# MSP-EXP430F5529LP.net
KiCad netlist of a schematic drawn in EAGLE
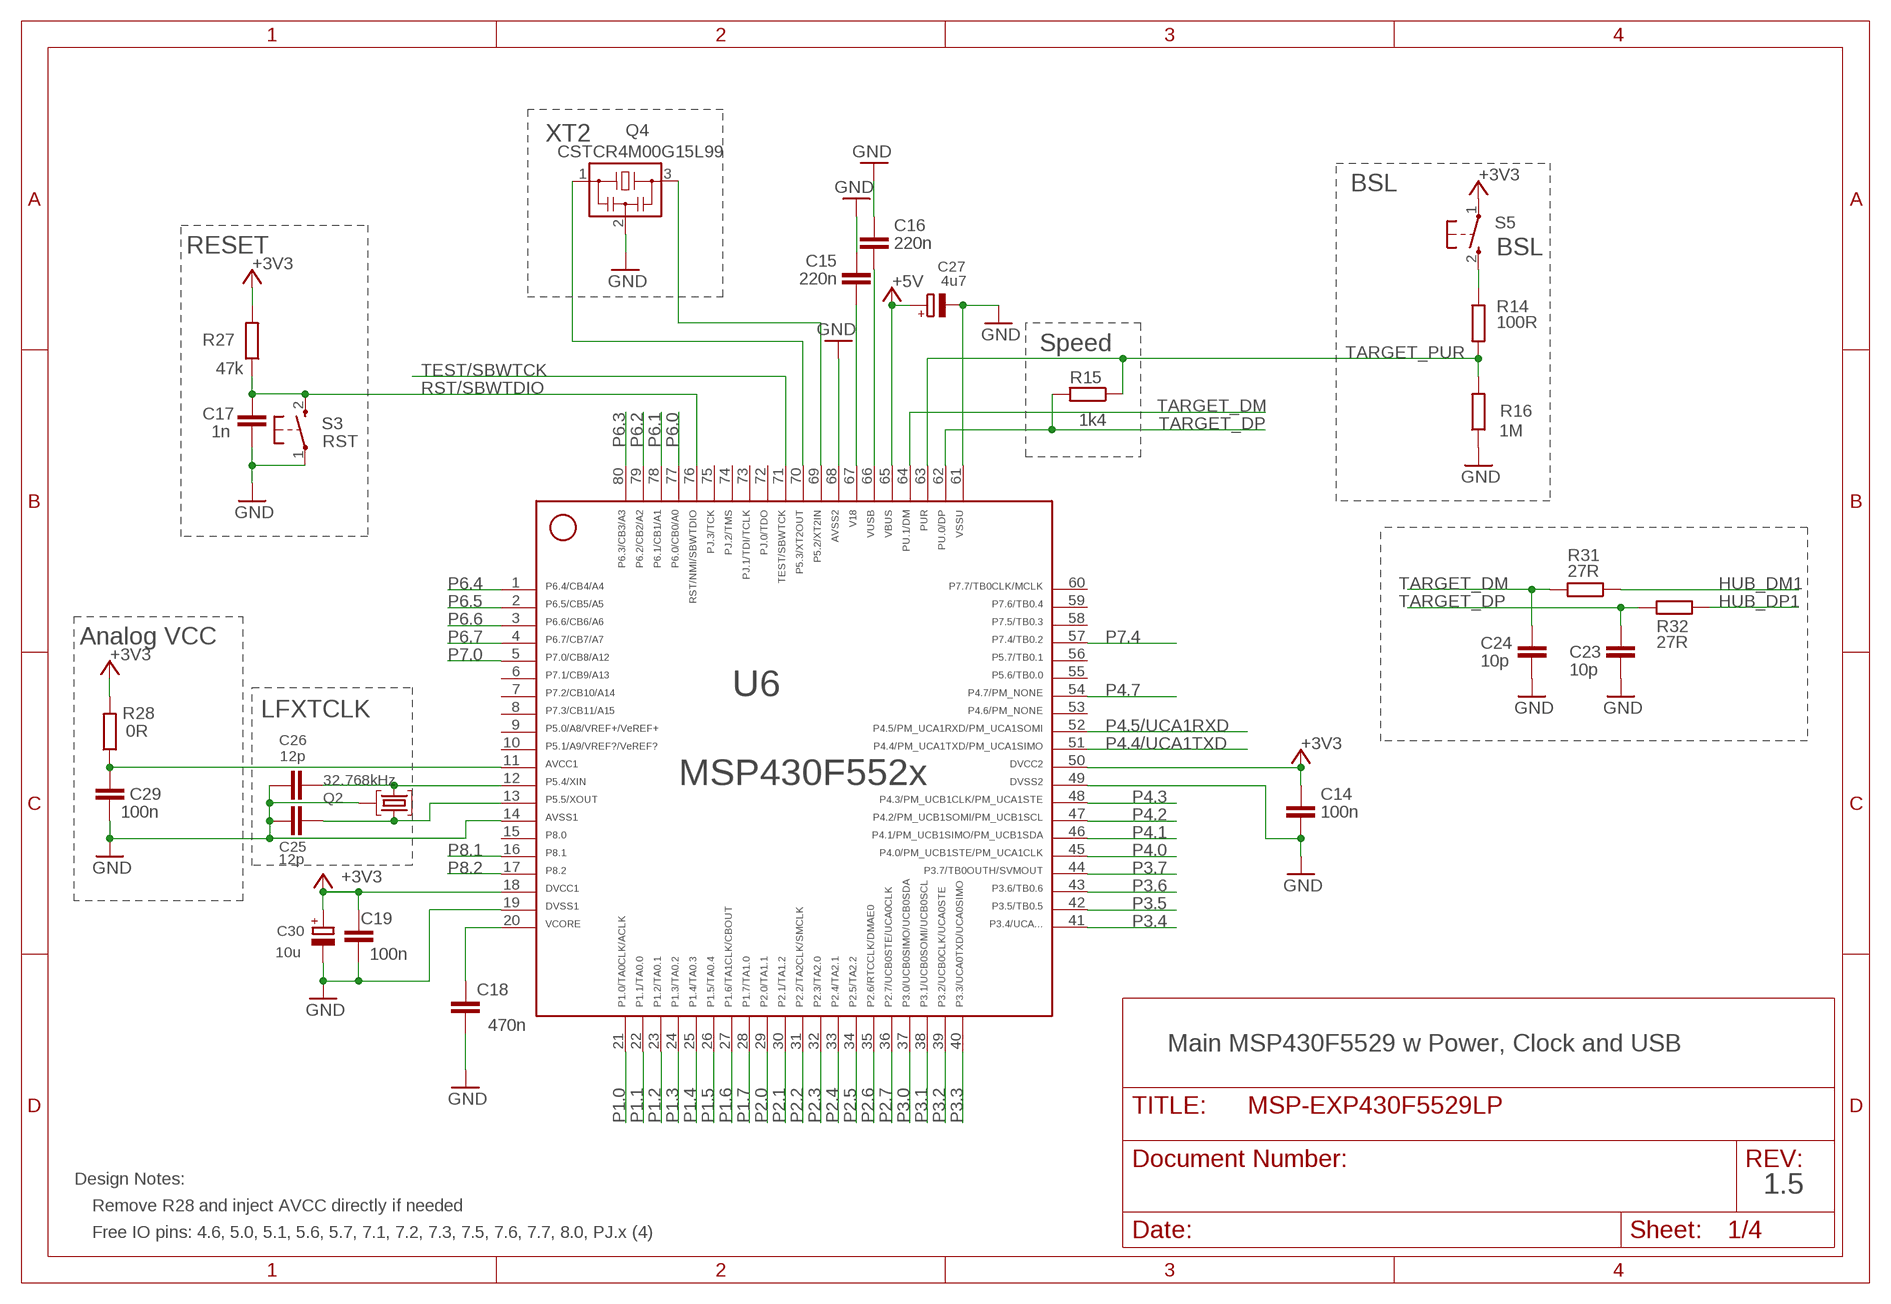
[diagram p0: schematic, sheet 1]
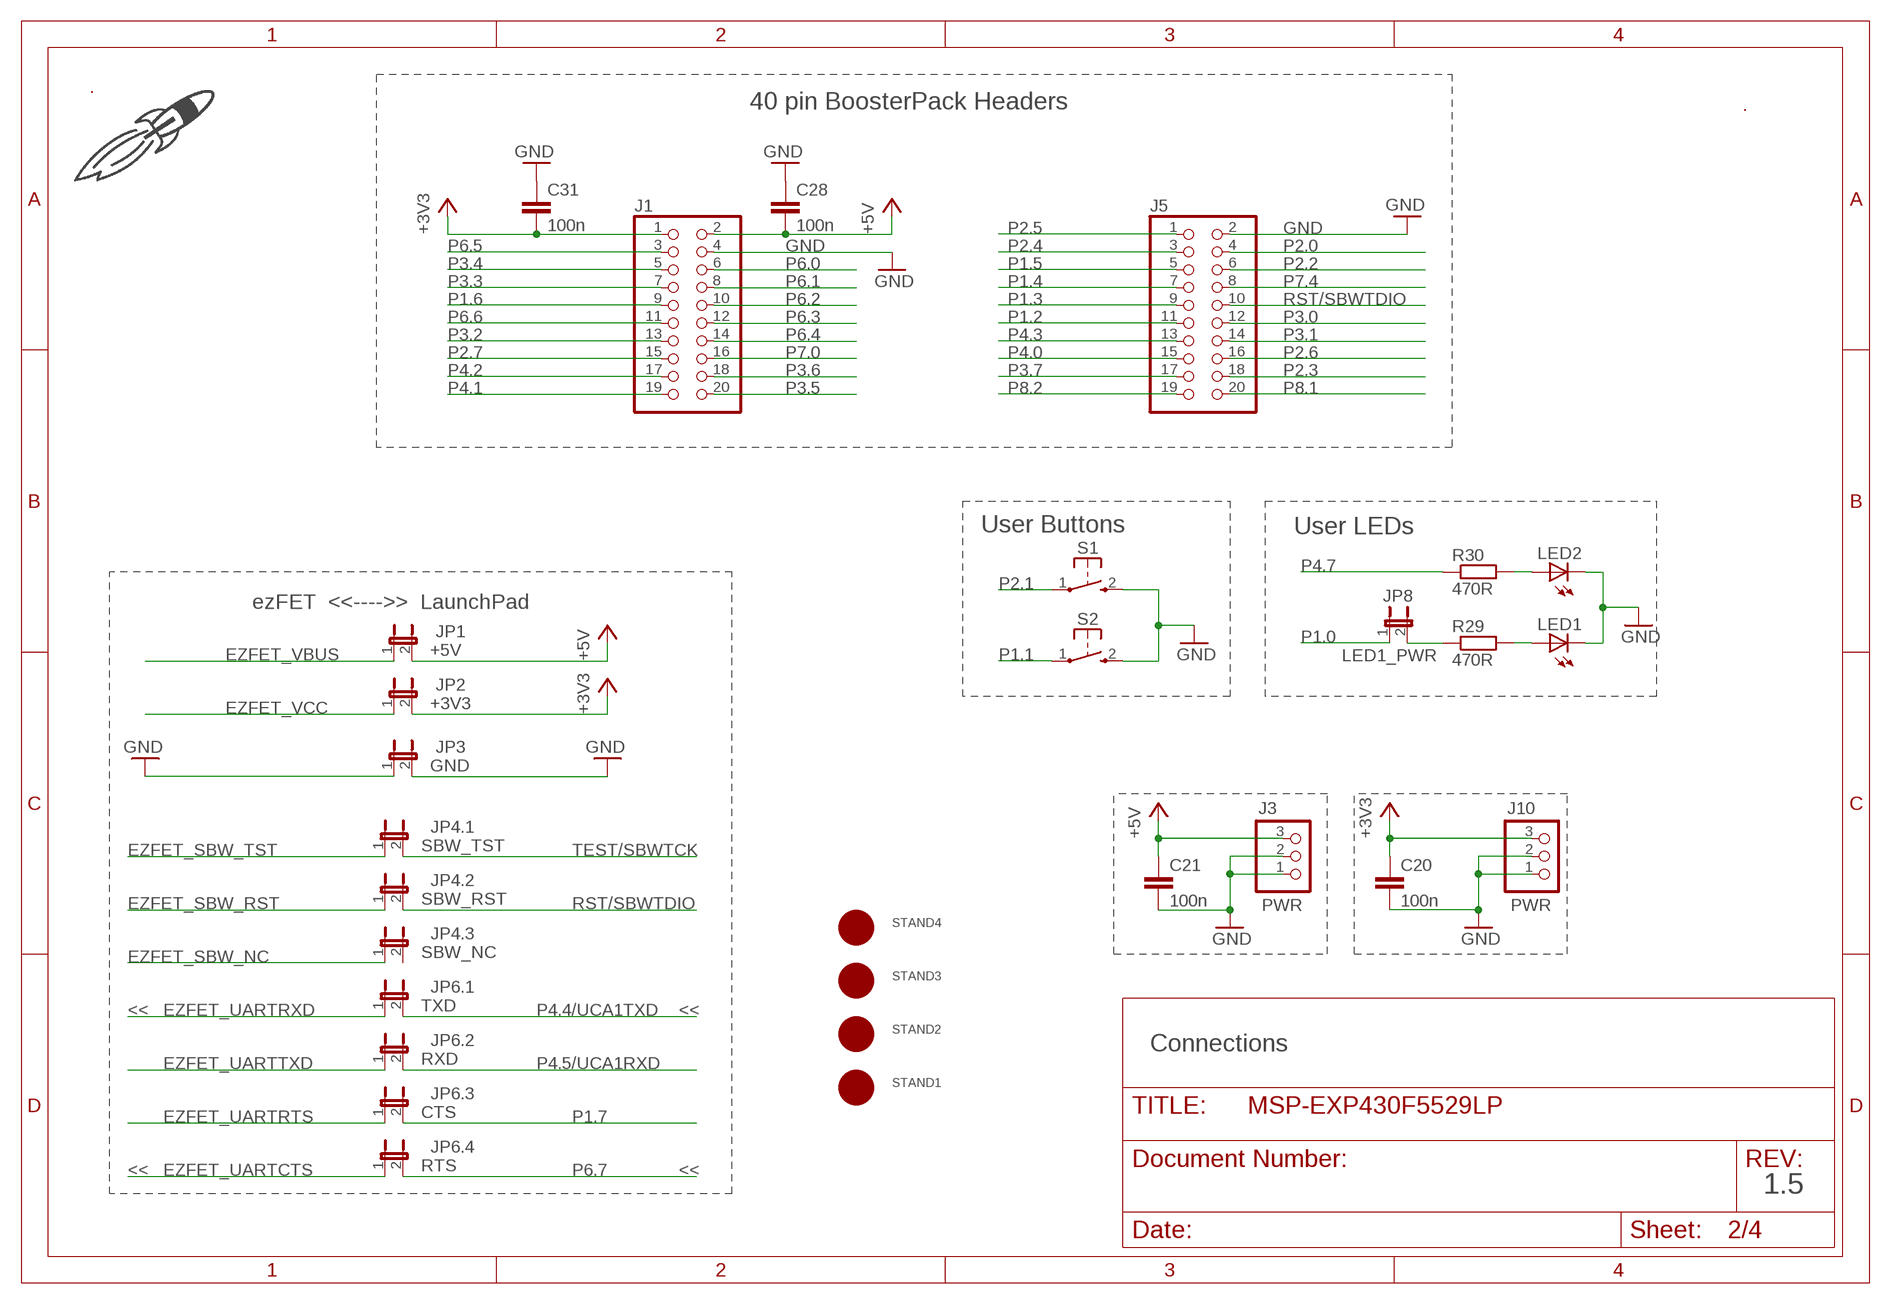
[diagram p1: schematic, sheet 2]
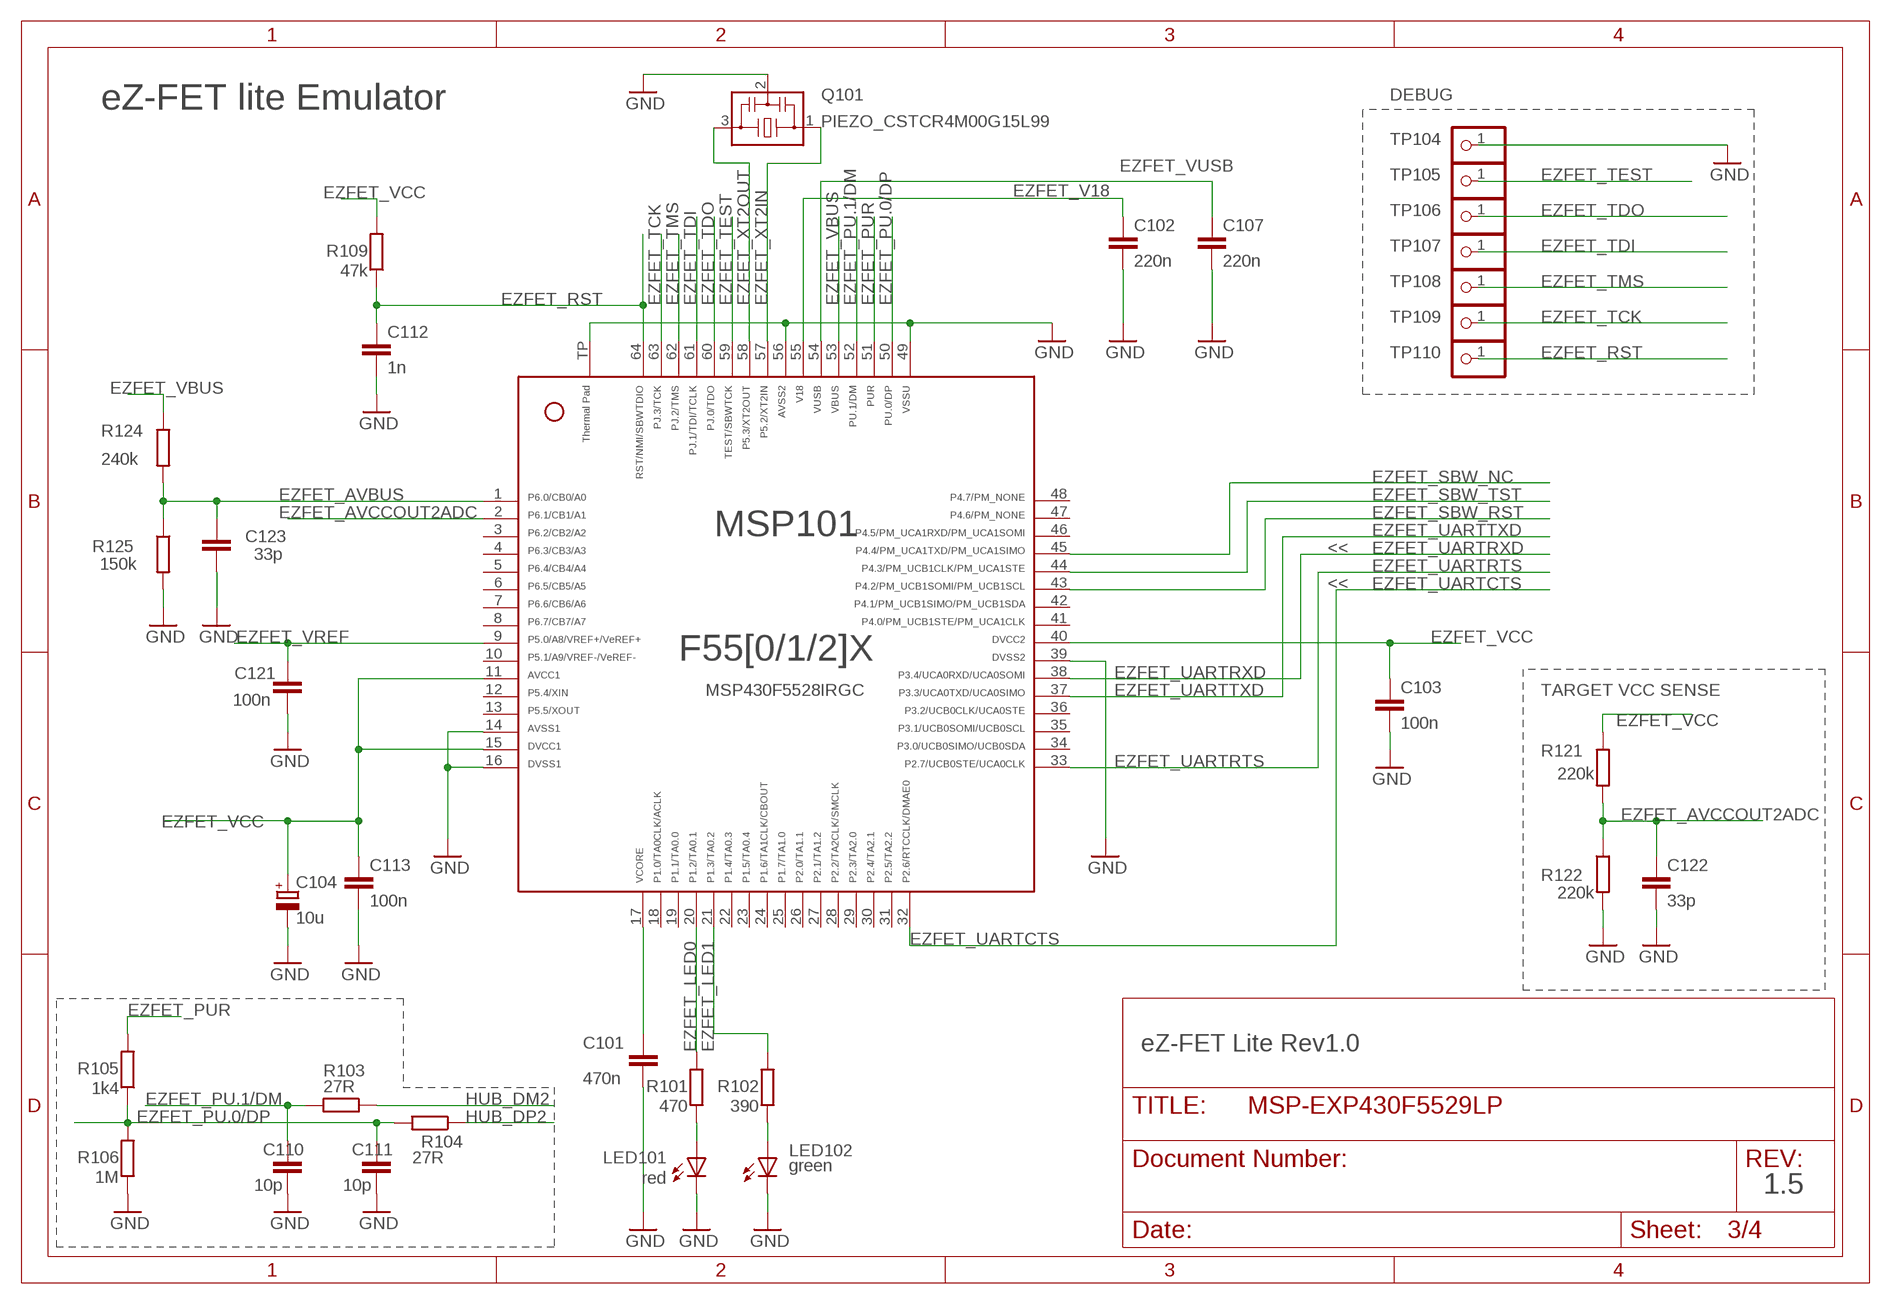
[diagram p2: schematic, sheet 3]
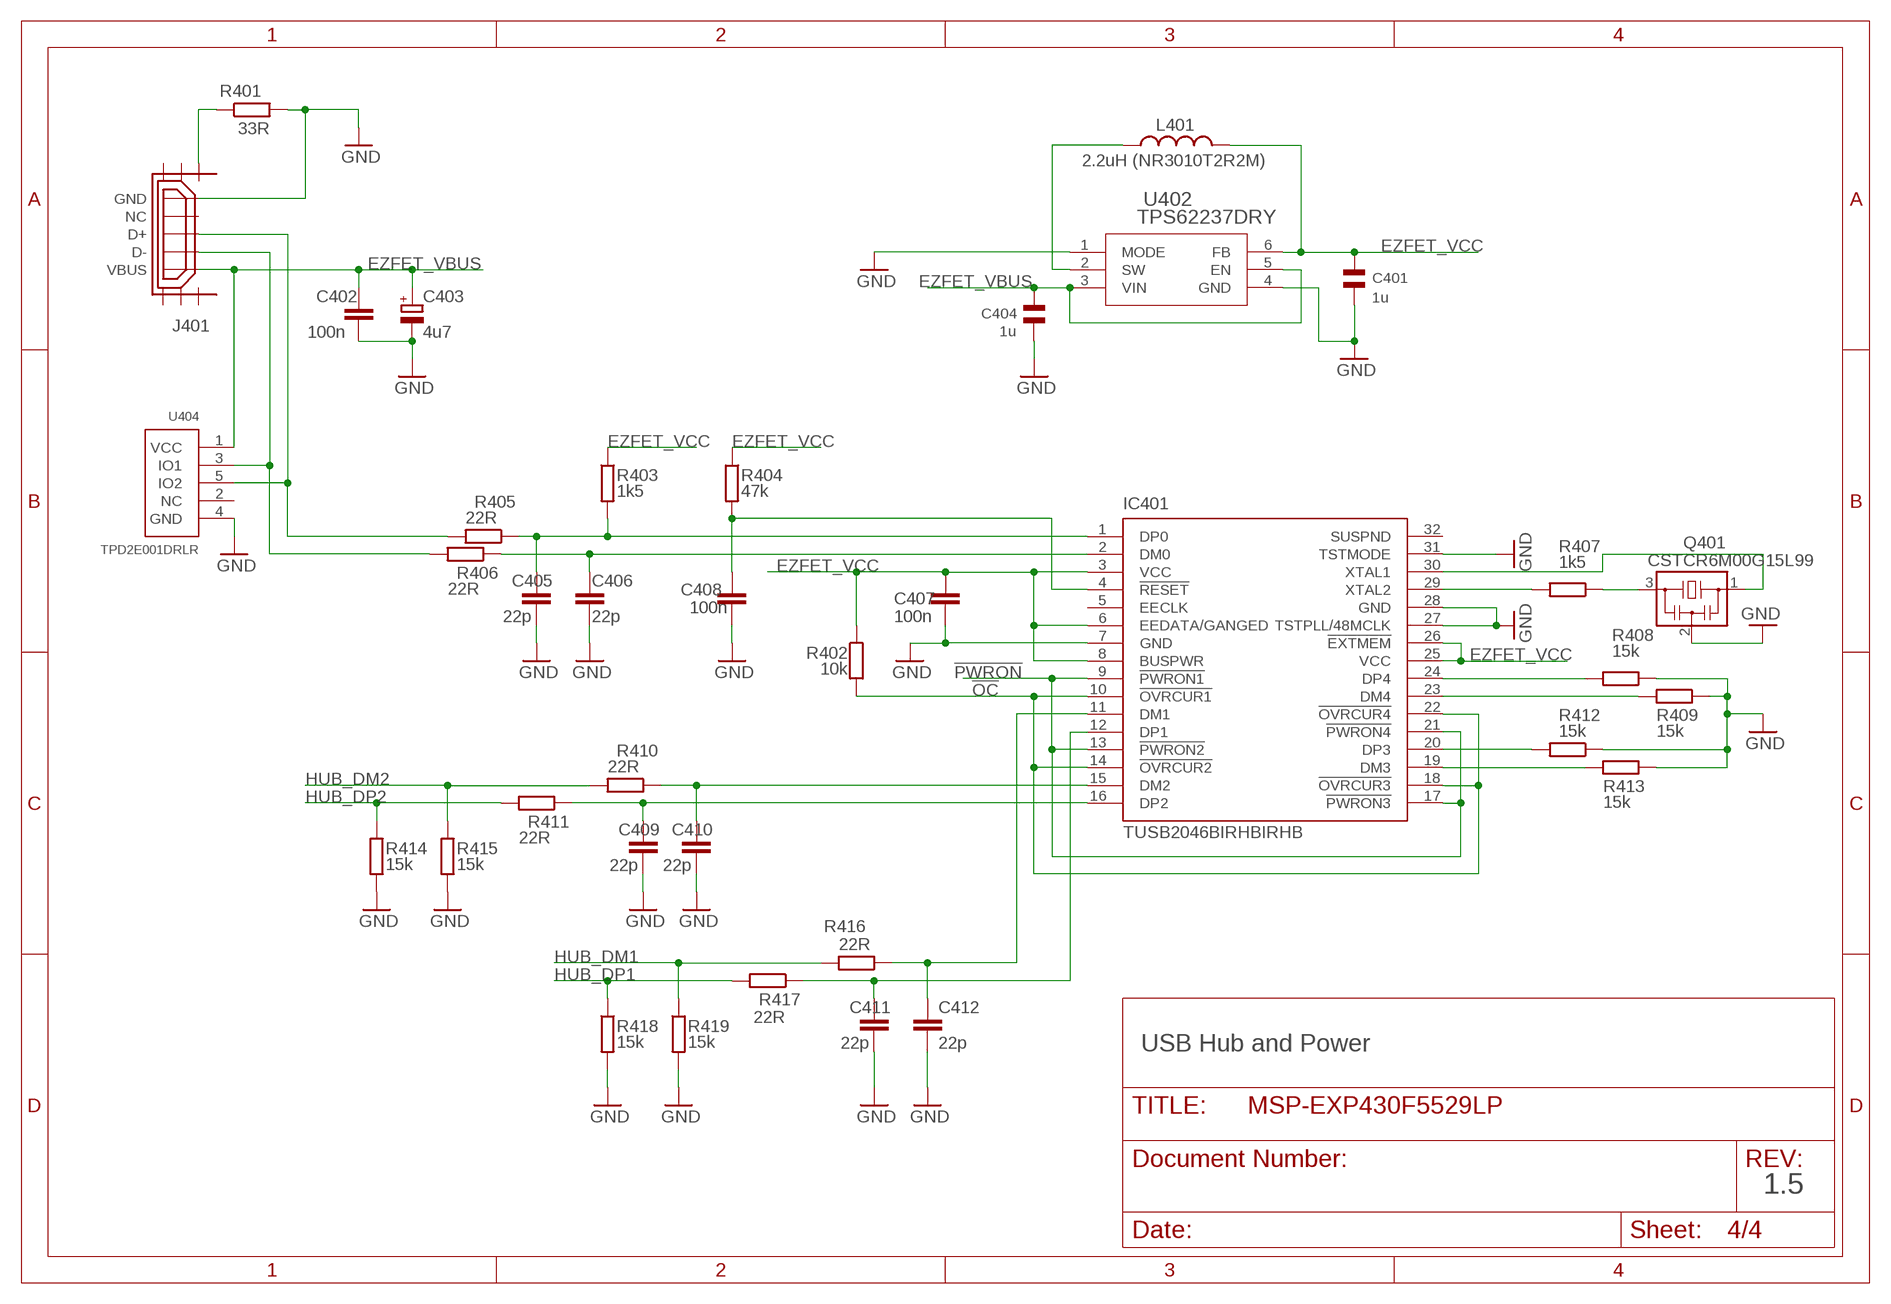
[diagram p3: schematic, sheet 4]

(export (version "E")
  (design (tool "Eeschema 10.0.6"))
  (components
    (comp (ref "C20")
      (value "100n")
      (footprint "eagle-import:C0402")
      (libsource (lib "eagle-import") (part "C-EUC0402"))
    )
    (comp (ref "C21")
      (value "100n")
      (footprint "eagle-import:C0402")
      (libsource (lib "eagle-import") (part "C-EUC0402"))
    )
    (comp (ref "C28")
      (value "100n")
      (footprint "eagle-import:C0402")
      (libsource (lib "eagle-import") (part "C-EUC0402"))
    )
    (comp (ref "C31")
      (value "100n")
      (footprint "eagle-import:C0402")
      (libsource (lib "eagle-import") (part "C-EUC0402"))
    )
    (comp (ref "DRAW1")
      (value "LOGO-ROCKET-20X13MM-SCH-S")
      (footprint "eagle-import:LOGO-ROCKET-10X7MM-BRD")
      (libsource (lib "eagle-import") (part "LOGO-ROCKET-20X13MM-SCH-S"))
    )
    (comp (ref "J1")
      (value "PINHD-2X10")
      (footprint "eagle-import:2X10")
      (libsource (lib "eagle-import") (part "PINHD-2X10"))
    )
    (comp (ref "J3")
      (value "PWR")
      (footprint "eagle-import:1X03")
      (libsource (lib "eagle-import") (part "PINHD-1X3"))
    )
    (comp (ref "J5")
      (value "PINHD-2X10")
      (footprint "eagle-import:2X10")
      (libsource (lib "eagle-import") (part "PINHD-2X10"))
    )
    (comp (ref "J10")
      (value "PWR")
      (footprint "eagle-import:1X03")
      (libsource (lib "eagle-import") (part "PINHD-1X3"))
    )
    (comp (ref "JP1")
      (value "+5V")
      (footprint "eagle-import:JP1M")
      (libsource (lib "eagle-import") (part "JP1M"))
    )
    (comp (ref "JP2")
      (value "+3V3")
      (footprint "eagle-import:JP1M")
      (libsource (lib "eagle-import") (part "JP1M"))
    )
    (comp (ref "JP3")
      (value "GND")
      (footprint "eagle-import:JP1M")
      (libsource (lib "eagle-import") (part "JP1M"))
    )
    (comp (ref "JP4.1")
      (value "SBW_TST")
      (footprint "eagle-import:JP1M")
      (libsource (lib "eagle-import") (part "JP1M"))
    )
    (comp (ref "JP4.2")
      (value "SBW_RST")
      (footprint "eagle-import:JP1M")
      (libsource (lib "eagle-import") (part "JP1M"))
    )
    (comp (ref "JP4.3")
      (value "SBW_NC")
      (footprint "eagle-import:JP1M")
      (libsource (lib "eagle-import") (part "JP1M"))
    )
    (comp (ref "JP6.1")
      (value "TXD")
      (footprint "eagle-import:JP1M")
      (libsource (lib "eagle-import") (part "JP1M"))
    )
    (comp (ref "JP6.2")
      (value "RXD")
      (footprint "eagle-import:JP1M")
      (libsource (lib "eagle-import") (part "JP1M"))
    )
    (comp (ref "JP6.3")
      (value "CTS")
      (footprint "eagle-import:JP1M")
      (libsource (lib "eagle-import") (part "JP1M"))
    )
    (comp (ref "JP6.4")
      (value "RTS")
      (footprint "eagle-import:JP1M")
      (libsource (lib "eagle-import") (part "JP1M"))
    )
    (comp (ref "JP8")
      (value "LED1_PWR")
      (footprint "eagle-import:JP1")
      (libsource (lib "eagle-import") (part "JP1E"))
    )
    (comp (ref "LED1")
      (value "LEDCHIP-LED0603")
      (footprint "eagle-import:CHIP-LED0603")
      (libsource (lib "eagle-import") (part "LEDCHIP-LED0603"))
    )
    (comp (ref "LED2")
      (value "LEDCHIP-LED0603")
      (footprint "eagle-import:CHIP-LED0603")
      (libsource (lib "eagle-import") (part "LEDCHIP-LED0603"))
    )
    (comp (ref "R29")
      (value "470R")
      (footprint "eagle-import:R0402")
      (libsource (lib "eagle-import") (part "R-EU_R0402"))
    )
    (comp (ref "R30")
      (value "470R")
      (footprint "eagle-import:R0402")
      (libsource (lib "eagle-import") (part "R-EU_R0402"))
    )
    (comp (ref "S1")
      (value "PB")
      (footprint "eagle-import:PBTH")
      (libsource (lib "eagle-import") (part "PB"))
    )
    (comp (ref "S2")
      (value "PB")
      (footprint "eagle-import:PBTH")
      (libsource (lib "eagle-import") (part "PB"))
    )
    (comp (ref "STAND1")
      (value "MOUNT")
      (footprint "eagle-import:MOUNTHOLE_110MIL")
      (libsource (lib "eagle-import") (part "MOUNT"))
    )
    (comp (ref "STAND2")
      (value "MOUNT")
      (footprint "eagle-import:MOUNTHOLE_110MIL")
      (libsource (lib "eagle-import") (part "MOUNT"))
    )
    (comp (ref "STAND3")
      (value "MOUNT")
      (footprint "eagle-import:MOUNTHOLE_110MIL")
      (libsource (lib "eagle-import") (part "MOUNT"))
    )
    (comp (ref "STAND4")
      (value "MOUNT")
      (footprint "eagle-import:MOUNTHOLE_110MIL")
      (libsource (lib "eagle-import") (part "MOUNT"))
    )
    (comp (ref "U$3")
      (value "5529_REAR_SILK_REV1_5_FINAL")
      (footprint "eagle-import:5529_REAR_SILK_REV1_5_FINAL")
      (libsource (lib "eagle-import") (part "5529_REAR_SILK_REV1_5_FINAL"))
    )
    (comp (ref "U$4")
      (value "MS_TM")
      (footprint "eagle-import:MS_TM")
      (libsource (lib "eagle-import") (part "MS_TM"))
    )
    (comp (ref "C401")
      (value "1u")
      (footprint "eagle-import:CSMD0805")
      (libsource (lib "eagle-import") (part "CSMD0805"))
    )
    (comp (ref "C402")
      (value "100n")
      (footprint "eagle-import:C0402")
      (libsource (lib "eagle-import") (part "C-EUC0402"))
    )
    (comp (ref "C403")
      (value "4u7")
      (footprint "eagle-import:A_3216-18R")
      (libsource (lib "eagle-import") (part "CPOL-EUA/3216-18R"))
    )
    (comp (ref "C404")
      (value "1u")
      (footprint "eagle-import:CSMD0805")
      (libsource (lib "eagle-import") (part "CSMD0805"))
    )
    (comp (ref "C405")
      (value "22p")
      (footprint "eagle-import:C0402")
      (libsource (lib "eagle-import") (part "C-EUC0402"))
    )
    (comp (ref "C406")
      (value "22p")
      (footprint "eagle-import:C0402")
      (libsource (lib "eagle-import") (part "C-EUC0402"))
    )
    (comp (ref "C407")
      (value "100n")
      (footprint "eagle-import:C0402")
      (libsource (lib "eagle-import") (part "C-EUC0402"))
    )
    (comp (ref "C408")
      (value "100n")
      (footprint "eagle-import:C0402")
      (libsource (lib "eagle-import") (part "C-EUC0402"))
    )
    (comp (ref "C409")
      (value "22p")
      (footprint "eagle-import:C0402")
      (libsource (lib "eagle-import") (part "C-EUC0402"))
    )
    (comp (ref "C410")
      (value "22p")
      (footprint "eagle-import:C0402")
      (libsource (lib "eagle-import") (part "C-EUC0402"))
    )
    (comp (ref "C411")
      (value "22p")
      (footprint "eagle-import:C0402")
      (libsource (lib "eagle-import") (part "C-EUC0402"))
    )
    (comp (ref "C412")
      (value "22p")
      (footprint "eagle-import:C0402")
      (libsource (lib "eagle-import") (part "C-EUC0402"))
    )
    (comp (ref "IC401")
      (value "TUSB2046BIRHBIRHB")
      (footprint "eagle-import:RHB_S-PQFP-N32")
      (fields (field (name "MPN") "TUSB2046BIRHBT"))
      (libsource (lib "eagle-import") (part "TUSB2046BIRHBIRHB"))
    )
    (comp (ref "J401")
      (value "USB_MICRO_FLIPPED")
      (footprint "eagle-import:HIROSE-ZX62R-B-5P")
      (libsource (lib "eagle-import") (part "USB_MICRO_FLIPPED"))
    )
    (comp (ref "L401")
      (value "2.2uH (NR3010T2R2M)")
      (footprint "eagle-import:L-NR3010")
      (libsource (lib "eagle-import") (part "L-NR3010"))
    )
    (comp (ref "Q401")
      (value "CSTCR6M00G15L99")
      (footprint "eagle-import:MURATA-FILTER_CSTCR")
      (fields (field (name "MPN") "CSTCR6M00G53-R0"))
      (libsource (lib "eagle-import") (part "MURATA-FILTER_CSTCR6M00G53Z"))
    )
    (comp (ref "R401")
      (value "33R")
      (footprint "eagle-import:R0402")
      (libsource (lib "eagle-import") (part "R-EU_R0402"))
    )
    (comp (ref "R402")
      (value "10k")
      (footprint "eagle-import:R0402")
      (libsource (lib "eagle-import") (part "R-EU_R0402"))
    )
    (comp (ref "R403")
      (value "1k5")
      (footprint "eagle-import:R0402")
      (libsource (lib "eagle-import") (part "R-EU_R0402"))
    )
    (comp (ref "R404")
      (value "47k")
      (footprint "eagle-import:R0402")
      (libsource (lib "eagle-import") (part "R-EU_R0402"))
    )
    (comp (ref "R405")
      (value "22R")
      (footprint "eagle-import:R0402")
      (libsource (lib "eagle-import") (part "R-EU_R0402"))
    )
    (comp (ref "R406")
      (value "22R")
      (footprint "eagle-import:R0402")
      (libsource (lib "eagle-import") (part "R-EU_R0402"))
    )
    (comp (ref "R407")
      (value "1k5")
      (footprint "eagle-import:R0402")
      (libsource (lib "eagle-import") (part "R-EU_R0402"))
    )
    (comp (ref "R408")
      (value "15k")
      (footprint "eagle-import:R0402")
      (libsource (lib "eagle-import") (part "R-EU_R0402"))
    )
    (comp (ref "R409")
      (value "15k")
      (footprint "eagle-import:R0402")
      (libsource (lib "eagle-import") (part "R-EU_R0402"))
    )
    (comp (ref "R410")
      (value "22R")
      (footprint "eagle-import:R0402")
      (libsource (lib "eagle-import") (part "R-EU_R0402"))
    )
    (comp (ref "R411")
      (value "22R")
      (footprint "eagle-import:R0402")
      (libsource (lib "eagle-import") (part "R-EU_R0402"))
    )
    (comp (ref "R412")
      (value "15k")
      (footprint "eagle-import:R0402")
      (libsource (lib "eagle-import") (part "R-EU_R0402"))
    )
    (comp (ref "R413")
      (value "15k")
      (footprint "eagle-import:R0402")
      (libsource (lib "eagle-import") (part "R-EU_R0402"))
    )
    (comp (ref "R414")
      (value "15k")
      (footprint "eagle-import:R0402")
      (libsource (lib "eagle-import") (part "R-EU_R0402"))
    )
    (comp (ref "R415")
      (value "15k")
      (footprint "eagle-import:R0402")
      (libsource (lib "eagle-import") (part "R-EU_R0402"))
    )
    (comp (ref "R416")
      (value "22R")
      (footprint "eagle-import:R0402")
      (libsource (lib "eagle-import") (part "R-EU_R0402"))
    )
    (comp (ref "R417")
      (value "22R")
      (footprint "eagle-import:R0402")
      (libsource (lib "eagle-import") (part "R-EU_R0402"))
    )
    (comp (ref "R418")
      (value "15k")
      (footprint "eagle-import:R0402")
      (libsource (lib "eagle-import") (part "R-EU_R0402"))
    )
    (comp (ref "R419")
      (value "15k")
      (footprint "eagle-import:R0402")
      (libsource (lib "eagle-import") (part "R-EU_R0402"))
    )
    (comp (ref "U402")
      (value "TPS62237DRY")
      (footprint "eagle-import:DRY6")
      (fields
        (field (name "GENERIC_PART_NUMBER") "TPS62231")
        (field (name "MANUFACTURER") "Texas Instruments")
        (field (name "MANUFACTURER_PART_NUMBER") "tps62231_dry_6")
      )
      (libsource (lib "eagle-import") (part "TPS6223X_DRY_6"))
    )
    (comp (ref "U404")
      (value "TPD2E001DRLR")
      (footprint "eagle-import:TPD2E001-DRL")
      (libsource (lib "eagle-import") (part "TPD2E001"))
    )
    (comp (ref "C14")
      (value "100n")
      (footprint "eagle-import:C0402")
      (libsource (lib "eagle-import") (part "C-EUC0402"))
    )
    (comp (ref "C15")
      (value "220n")
      (footprint "eagle-import:C0402")
      (libsource (lib "eagle-import") (part "C-EUC0402"))
    )
    (comp (ref "C16")
      (value "220n")
      (footprint "eagle-import:C0402")
      (libsource (lib "eagle-import") (part "C-EUC0402"))
    )
    (comp (ref "C17")
      (value "1n")
      (footprint "eagle-import:C0402")
      (libsource (lib "eagle-import") (part "C-EUC0402"))
    )
    (comp (ref "C18")
      (value "470n")
      (footprint "eagle-import:C0402")
      (libsource (lib "eagle-import") (part "C-EUC0402"))
    )
    (comp (ref "C19")
      (value "100n")
      (footprint "eagle-import:C0402")
      (libsource (lib "eagle-import") (part "C-EUC0402"))
    )
    (comp (ref "C23")
      (value "10p")
      (footprint "eagle-import:C0402")
      (libsource (lib "eagle-import") (part "C-EUC0402"))
    )
    (comp (ref "C24")
      (value "10p")
      (footprint "eagle-import:C0402")
      (libsource (lib "eagle-import") (part "C-EUC0402"))
    )
    (comp (ref "C25")
      (value "12p")
      (footprint "eagle-import:C0402")
      (libsource (lib "eagle-import") (part "C-EUC0402"))
    )
    (comp (ref "C26")
      (value "12p")
      (footprint "eagle-import:C0402")
      (libsource (lib "eagle-import") (part "C-EUC0402"))
    )
    (comp (ref "C27")
      (value "4u7")
      (footprint "eagle-import:A_3216-18R")
      (libsource (lib "eagle-import") (part "CPOL-EUA/3216-18R"))
    )
    (comp (ref "C29")
      (value "100n")
      (footprint "eagle-import:C0402")
      (libsource (lib "eagle-import") (part "C-EUC0402"))
    )
    (comp (ref "C30")
      (value "10u")
      (footprint "eagle-import:A_3216-18R")
      (libsource (lib "eagle-import") (part "CPOL-EUA/3216-18R"))
    )
    (comp (ref "Q2")
      (value "32.768kHz")
      (footprint "eagle-import:MS3V-T1R")
      (libsource (lib "eagle-import") (part "MS3V-T1R"))
    )
    (comp (ref "Q4")
      (value "CSTCR4M00G15L99")
      (footprint "eagle-import:MURATA-FILTER_CSTCR")
      (fields (field (name "MPN") "CSTCR6M00G53-R0"))
      (libsource (lib "eagle-import") (part "MURATA-FILTER_CSTCR6M00G53Z"))
    )
    (comp (ref "R14")
      (value "100R")
      (footprint "eagle-import:R0402")
      (libsource (lib "eagle-import") (part "R-EU_R0402"))
    )
    (comp (ref "R15")
      (value "1k4")
      (footprint "eagle-import:R0402")
      (libsource (lib "eagle-import") (part "R-EU_R0402"))
    )
    (comp (ref "R16")
      (value "1M")
      (footprint "eagle-import:R0402")
      (libsource (lib "eagle-import") (part "R-EU_R0402"))
    )
    (comp (ref "R27")
      (value "47k")
      (footprint "eagle-import:R0402")
      (libsource (lib "eagle-import") (part "R-EU_R0402"))
    )
    (comp (ref "R28")
      (value "0R")
      (footprint "eagle-import:R0402")
      (libsource (lib "eagle-import") (part "R-EU_R0402"))
    )
    (comp (ref "R31")
      (value "27R")
      (footprint "eagle-import:R0402")
      (libsource (lib "eagle-import") (part "R-EU_R0402"))
    )
    (comp (ref "R32")
      (value "27R")
      (footprint "eagle-import:R0402")
      (libsource (lib "eagle-import") (part "R-EU_R0402"))
    )
    (comp (ref "S3")
      (value "RST")
      (footprint "eagle-import:PBTH")
      (libsource (lib "eagle-import") (part "PB"))
    )
    (comp (ref "S5")
      (value "BSL")
      (footprint "eagle-import:PBTH")
      (libsource (lib "eagle-import") (part "PB"))
    )
    (comp (ref "U6")
      (value "MSP430F5529IPNR")
      (footprint "eagle-import:PN80")
      (libsource (lib "eagle-import") (part "F552X---PN80"))
    )
    (comp (ref "C101")
      (value "470n")
      (footprint "eagle-import:C0402")
      (libsource (lib "eagle-import") (part "C-EUC0402"))
    )
    (comp (ref "C102")
      (value "220n")
      (footprint "eagle-import:C0402")
      (libsource (lib "eagle-import") (part "C-EUC0402"))
    )
    (comp (ref "C103")
      (value "100n")
      (footprint "eagle-import:C0402")
      (libsource (lib "eagle-import") (part "C-EUC0402"))
    )
    (comp (ref "C104")
      (value "10u")
      (footprint "eagle-import:A_3216-18R")
      (libsource (lib "eagle-import") (part "CPOL-EUA/3216-18R"))
    )
    (comp (ref "C107")
      (value "220n")
      (footprint "eagle-import:C0402")
      (libsource (lib "eagle-import") (part "C-EUC0402"))
    )
    (comp (ref "C110")
      (value "10p")
      (footprint "eagle-import:C0402")
      (libsource (lib "eagle-import") (part "C-EUC0402"))
    )
    (comp (ref "C111")
      (value "10p")
      (footprint "eagle-import:C0402")
      (libsource (lib "eagle-import") (part "C-EUC0402"))
    )
    (comp (ref "C112")
      (value "1n")
      (footprint "eagle-import:C0402")
      (libsource (lib "eagle-import") (part "C-EUC0402"))
    )
    (comp (ref "C113")
      (value "100n")
      (footprint "eagle-import:C0402")
      (libsource (lib "eagle-import") (part "C-EUC0402"))
    )
    (comp (ref "C121")
      (value "100n")
      (footprint "eagle-import:C0402")
      (libsource (lib "eagle-import") (part "C-EUC0402"))
    )
    (comp (ref "C122")
      (value "33p")
      (footprint "eagle-import:C0402")
      (libsource (lib "eagle-import") (part "C-EUC0402"))
    )
    (comp (ref "C123")
      (value "33p")
      (footprint "eagle-import:C0402")
      (libsource (lib "eagle-import") (part "C-EUC0402"))
    )
    (comp (ref "LED101")
      (value "red")
      (footprint "eagle-import:CHIP-LED0603")
      (libsource (lib "eagle-import") (part "LEDCHIP-LED0603"))
    )
    (comp (ref "LED102")
      (value "green")
      (footprint "eagle-import:CHIP-LED0603")
      (libsource (lib "eagle-import") (part "LEDCHIP-LED0603"))
    )
    (comp (ref "MSP101")
      (value "MSP430F5528IRGC")
      (footprint "eagle-import:RGC64")
      (libsource (lib "eagle-import") (part "F55[0/1/2]X---RGC64"))
    )
    (comp (ref "Q101")
      (value "PIEZO_CSTCR4M00G15L99")
      (footprint "eagle-import:MURATA-FILTER_CSTCR")
      (fields (field (name "MPN") "CSTCR6M00G53-R0"))
      (libsource (lib "eagle-import") (part "MURATA-FILTER_CSTCR6M00G53Z"))
    )
    (comp (ref "R101")
      (value "470")
      (footprint "eagle-import:R0402")
      (libsource (lib "eagle-import") (part "R-EU_R0402"))
    )
    (comp (ref "R102")
      (value "390")
      (footprint "eagle-import:R0402")
      (libsource (lib "eagle-import") (part "R-EU_R0402"))
    )
    (comp (ref "R103")
      (value "27R")
      (footprint "eagle-import:R0402")
      (libsource (lib "eagle-import") (part "R-EU_R0402"))
    )
    (comp (ref "R104")
      (value "27R")
      (footprint "eagle-import:R0402")
      (libsource (lib "eagle-import") (part "R-EU_R0402"))
    )
    (comp (ref "R105")
      (value "1k4")
      (footprint "eagle-import:R0402")
      (libsource (lib "eagle-import") (part "R-EU_R0402"))
    )
    (comp (ref "R106")
      (value "1M")
      (footprint "eagle-import:R0402")
      (libsource (lib "eagle-import") (part "R-EU_R0402"))
    )
    (comp (ref "R109")
      (value "47k")
      (footprint "eagle-import:R0402")
      (libsource (lib "eagle-import") (part "R-EU_R0402"))
    )
    (comp (ref "R121")
      (value "220k")
      (footprint "eagle-import:R0402")
      (libsource (lib "eagle-import") (part "R-EU_R0402"))
    )
    (comp (ref "R122")
      (value "220k")
      (footprint "eagle-import:R0402")
      (libsource (lib "eagle-import") (part "R-EU_R0402"))
    )
    (comp (ref "R124")
      (value "240k")
      (footprint "eagle-import:R0402")
      (libsource (lib "eagle-import") (part "R-EU_R0402"))
    )
    (comp (ref "R125")
      (value "150k")
      (footprint "eagle-import:R0402")
      (libsource (lib "eagle-import") (part "R-EU_R0402"))
    )
    (comp (ref "TP104")
      (value "TEST_PIN2")
      (footprint "eagle-import:1X01")
      (libsource (lib "eagle-import") (part "PINHD-1X1"))
    )
    (comp (ref "TP105")
      (value "TEST_PIN2")
      (footprint "eagle-import:1X01")
      (libsource (lib "eagle-import") (part "PINHD-1X1"))
    )
    (comp (ref "TP106")
      (value "TEST_PIN2")
      (footprint "eagle-import:1X01")
      (libsource (lib "eagle-import") (part "PINHD-1X1"))
    )
    (comp (ref "TP107")
      (value "TEST_PIN2")
      (footprint "eagle-import:1X01")
      (libsource (lib "eagle-import") (part "PINHD-1X1"))
    )
    (comp (ref "TP108")
      (value "TEST_PIN2")
      (footprint "eagle-import:1X01")
      (libsource (lib "eagle-import") (part "PINHD-1X1"))
    )
    (comp (ref "TP109")
      (value "TEST_PIN2")
      (footprint "eagle-import:1X01")
      (libsource (lib "eagle-import") (part "PINHD-1X1"))
    )
    (comp (ref "TP110")
      (value "TEST_PIN2")
      (footprint "eagle-import:1X01")
      (libsource (lib "eagle-import") (part "PINHD-1X1"))
    )
  )
  (nets
    (net (code "1") (name "+3V3") (class "Default")
      (node (ref "C14") (pin "1") (pinfunction "1_1") (pintype "passive"))
      (node (ref "C19") (pin "2") (pinfunction "2_2") (pintype "passive"))
      (node (ref "C20") (pin "1") (pinfunction "1_1") (pintype "passive"))
      (node (ref "C30") (pin "+") (pinfunction "+_+") (pintype "passive"))
      (node (ref "C31") (pin "2") (pinfunction "2_2") (pintype "passive"))
      (node (ref "J1") (pin "1") (pinfunction "1_1") (pintype "passive"))
      (node (ref "J10") (pin "3") (pinfunction "3_3") (pintype "passive"))
      (node (ref "JP2") (pin "2") (pinfunction "2_2") (pintype "passive"))
      (node (ref "R27") (pin "2") (pinfunction "2_2") (pintype "passive"))
      (node (ref "R28") (pin "2") (pinfunction "2_2") (pintype "passive"))
      (node (ref "S5") (pin "1") (pinfunction "P_1") (pintype "passive"))
      (node (ref "U6") (pin "18") (pinfunction "18_18") (pintype "power_in"))
      (node (ref "U6") (pin "50") (pinfunction "50_50") (pintype "power_in"))
    )
    (net (code "2") (name "+5V") (class "Default")
      (node (ref "C21") (pin "1") (pinfunction "1_1") (pintype "passive"))
      (node (ref "C27") (pin "+") (pinfunction "+_+") (pintype "passive"))
      (node (ref "C28") (pin "2") (pinfunction "2_2") (pintype "passive"))
      (node (ref "J1") (pin "2") (pinfunction "2_2") (pintype "passive"))
      (node (ref "J3") (pin "3") (pinfunction "3_3") (pintype "passive"))
      (node (ref "JP1") (pin "2") (pinfunction "2_2") (pintype "passive"))
      (node (ref "U6") (pin "65") (pinfunction "65_65") (pintype "power_in"))
    )
    (net (code "3") (name "EZFET_AVBUS") (class "Default")
      (node (ref "C123") (pin "2") (pinfunction "2_2") (pintype "passive"))
      (node (ref "MSP101") (pin "1") (pinfunction "1_1") (pintype "bidirectional"))
      (node (ref "R124") (pin "2") (pinfunction "2_2") (pintype "passive"))
      (node (ref "R125") (pin "1") (pinfunction "1_1") (pintype "passive"))
    )
    (net (code "4") (name "EZFET_AVCCOUT2ADC") (class "Default")
      (node (ref "C122") (pin "2") (pinfunction "2_2") (pintype "passive"))
      (node (ref "MSP101") (pin "2") (pinfunction "2_2") (pintype "bidirectional"))
      (node (ref "R121") (pin "2") (pinfunction "2_2") (pintype "passive"))
      (node (ref "R122") (pin "1") (pinfunction "1_1") (pintype "passive"))
    )
    (net (code "5") (name "EZFET_LED0") (class "Default")
      (node (ref "MSP101") (pin "20") (pinfunction "20_20") (pintype "bidirectional"))
      (node (ref "R101") (pin "2") (pinfunction "2_2") (pintype "passive"))
    )
    (net (code "6") (name "EZFET_LED1") (class "Default")
      (node (ref "MSP101") (pin "21") (pinfunction "21_21") (pintype "bidirectional"))
      (node (ref "R102") (pin "2") (pinfunction "2_2") (pintype "passive"))
    )
    (net (code "7") (name "EZFET_PU.0{slash}DP") (class "Default")
      (node (ref "C111") (pin "1") (pinfunction "1_1") (pintype "passive"))
      (node (ref "MSP101") (pin "50") (pinfunction "50_50") (pintype "bidirectional"))
      (node (ref "R104") (pin "2") (pinfunction "2_2") (pintype "passive"))
      (node (ref "R105") (pin "1") (pinfunction "1_1") (pintype "passive"))
      (node (ref "R106") (pin "2") (pinfunction "2_2") (pintype "passive"))
    )
    (net (code "8") (name "EZFET_PU.1{slash}DM") (class "Default")
      (node (ref "C110") (pin "1") (pinfunction "1_1") (pintype "passive"))
      (node (ref "MSP101") (pin "52") (pinfunction "52_52") (pintype "bidirectional"))
      (node (ref "R103") (pin "2") (pinfunction "2_2") (pintype "passive"))
    )
    (net (code "9") (name "EZFET_PUR") (class "Default")
      (node (ref "MSP101") (pin "51") (pinfunction "51_51") (pintype "bidirectional"))
      (node (ref "R105") (pin "2") (pinfunction "2_2") (pintype "passive"))
    )
    (net (code "10") (name "EZFET_RST") (class "Default")
      (node (ref "C112") (pin "1") (pinfunction "1_1") (pintype "passive"))
      (node (ref "MSP101") (pin "64") (pinfunction "64_64") (pintype "bidirectional"))
      (node (ref "R109") (pin "1") (pinfunction "1_1") (pintype "passive"))
      (node (ref "TP110") (pin "1") (pinfunction "1_1") (pintype "passive"))
    )
    (net (code "11") (name "EZFET_SBW_NC") (class "Default")
      (node (ref "JP4.3") (pin "1") (pinfunction "1_1") (pintype "passive"))
      (node (ref "MSP101") (pin "45") (pinfunction "45_45") (pintype "bidirectional"))
    )
    (net (code "12") (name "EZFET_SBW_RST") (class "Default")
      (node (ref "JP4.2") (pin "1") (pinfunction "1_1") (pintype "passive"))
      (node (ref "MSP101") (pin "43") (pinfunction "43_43") (pintype "bidirectional"))
    )
    (net (code "13") (name "EZFET_SBW_TST") (class "Default")
      (node (ref "JP4.1") (pin "1") (pinfunction "1_1") (pintype "passive"))
      (node (ref "MSP101") (pin "44") (pinfunction "44_44") (pintype "bidirectional"))
    )
    (net (code "14") (name "EZFET_TCK") (class "Default")
      (node (ref "MSP101") (pin "63") (pinfunction "63_63") (pintype "bidirectional"))
      (node (ref "TP109") (pin "1") (pinfunction "1_1") (pintype "passive"))
    )
    (net (code "15") (name "EZFET_TDI") (class "Default")
      (node (ref "MSP101") (pin "61") (pinfunction "61_61") (pintype "bidirectional"))
      (node (ref "TP107") (pin "1") (pinfunction "1_1") (pintype "passive"))
    )
    (net (code "16") (name "EZFET_TDO") (class "Default")
      (node (ref "MSP101") (pin "60") (pinfunction "60_60") (pintype "bidirectional"))
      (node (ref "TP106") (pin "1") (pinfunction "1_1") (pintype "passive"))
    )
    (net (code "17") (name "EZFET_TEST") (class "Default")
      (node (ref "MSP101") (pin "59") (pinfunction "59_59") (pintype "input"))
      (node (ref "TP105") (pin "1") (pinfunction "1_1") (pintype "passive"))
    )
    (net (code "18") (name "EZFET_TMS") (class "Default")
      (node (ref "MSP101") (pin "62") (pinfunction "62_62") (pintype "bidirectional"))
      (node (ref "TP108") (pin "1") (pinfunction "1_1") (pintype "passive"))
    )
    (net (code "19") (name "EZFET_UARTCTS") (class "Default")
      (node (ref "JP6.4") (pin "1") (pinfunction "1_1") (pintype "passive"))
      (node (ref "MSP101") (pin "32") (pinfunction "32_32") (pintype "bidirectional"))
    )
    (net (code "20") (name "EZFET_UARTRTS") (class "Default")
      (node (ref "JP6.3") (pin "1") (pinfunction "1_1") (pintype "passive"))
      (node (ref "MSP101") (pin "33") (pinfunction "33_33") (pintype "bidirectional"))
    )
    (net (code "21") (name "EZFET_UARTRXD") (class "Default")
      (node (ref "JP6.1") (pin "1") (pinfunction "1_1") (pintype "passive"))
      (node (ref "MSP101") (pin "38") (pinfunction "38_38") (pintype "bidirectional"))
    )
    (net (code "22") (name "EZFET_UARTTXD") (class "Default")
      (node (ref "JP6.2") (pin "1") (pinfunction "1_1") (pintype "passive"))
      (node (ref "MSP101") (pin "37") (pinfunction "37_37") (pintype "bidirectional"))
    )
    (net (code "23") (name "EZFET_V18") (class "Default")
      (node (ref "C102") (pin "1") (pinfunction "1_1") (pintype "passive"))
      (node (ref "MSP101") (pin "55") (pinfunction "55_55") (pintype "power_in"))
    )
    (net (code "24") (name "EZFET_VBUS") (class "Default")
      (node (ref "C402") (pin "1") (pinfunction "1_1") (pintype "passive"))
      (node (ref "C403") (pin "+") (pinfunction "+_+") (pintype "passive"))
      (node (ref "C404") (pin "2") (pinfunction "2_2") (pintype "passive"))
      (node (ref "J401") (pin "VBUS") (pinfunction "VBUS_VBUS") (pintype "input"))
      (node (ref "JP1") (pin "1") (pinfunction "1_1") (pintype "passive"))
      (node (ref "MSP101") (pin "53") (pinfunction "53_53") (pintype "power_in"))
      (node (ref "R124") (pin "1") (pinfunction "1_1") (pintype "passive"))
      (node (ref "U402") (pin "3") (pinfunction "VIN_3") (pintype "power_in"))
      (node (ref "U402") (pin "5") (pinfunction "EN_5") (pintype "input"))
      (node (ref "U404") (pin "1") (pinfunction "VCC_1") (pintype "power_in"))
    )
    (net (code "25") (name "EZFET_VCC") (class "Default")
      (node (ref "C103") (pin "1") (pinfunction "1_1") (pintype "passive"))
      (node (ref "C104") (pin "+") (pinfunction "+_+") (pintype "passive"))
      (node (ref "C113") (pin "1") (pinfunction "1_1") (pintype "passive"))
      (node (ref "C401") (pin "2") (pinfunction "2_2") (pintype "passive"))
      (node (ref "C407") (pin "1") (pinfunction "1_1") (pintype "passive"))
      (node (ref "IC401") (pin "25") (pinfunction "VCC_25") (pintype "power_in"))
      (node (ref "IC401") (pin "26") (pinfunction "~{EXTMEM}_26") (pintype "input"))
      (node (ref "IC401") (pin "3") (pinfunction "VCC_3") (pintype "power_in"))
      (node (ref "IC401") (pin "6") (pinfunction "EEDATA/GANGED_6") (pintype "bidirectional"))
      (node (ref "IC401") (pin "8") (pinfunction "BUSPWR_8") (pintype "input"))
      (node (ref "JP2") (pin "1") (pinfunction "1_1") (pintype "passive"))
      (node (ref "L401") (pin "P$2") (pinfunction "2_P$2") (pintype "passive"))
      (node (ref "MSP101") (pin "11") (pinfunction "11_11") (pintype "power_in"))
      (node (ref "MSP101") (pin "15") (pinfunction "15_15") (pintype "power_in"))
      (node (ref "MSP101") (pin "40") (pinfunction "40_40") (pintype "power_in"))
      (node (ref "R109") (pin "2") (pinfunction "2_2") (pintype "passive"))
      (node (ref "R121") (pin "1") (pinfunction "1_1") (pintype "passive"))
      (node (ref "R402") (pin "1") (pinfunction "1_1") (pintype "passive"))
      (node (ref "R403") (pin "1") (pinfunction "1_1") (pintype "passive"))
      (node (ref "R404") (pin "1") (pinfunction "1_1") (pintype "passive"))
      (node (ref "U402") (pin "6") (pinfunction "FB_6") (pintype "input"))
    )
    (net (code "26") (name "EZFET_VREF") (class "Default")
      (node (ref "C121") (pin "1") (pinfunction "1_1") (pintype "passive"))
      (node (ref "MSP101") (pin "9") (pinfunction "9_9") (pintype "bidirectional"))
    )
    (net (code "27") (name "EZFET_VUSB") (class "Default")
      (node (ref "C107") (pin "1") (pinfunction "1_1") (pintype "passive"))
      (node (ref "MSP101") (pin "54") (pinfunction "54_54") (pintype "power_in"))
    )
    (net (code "28") (name "EZFET_XT2IN") (class "Default")
      (node (ref "MSP101") (pin "57") (pinfunction "57_57") (pintype "bidirectional"))
      (node (ref "Q101") (pin "1") (pinfunction "1_1") (pintype "passive"))
    )
    (net (code "29") (name "EZFET_XT2OUT") (class "Default")
      (node (ref "MSP101") (pin "58") (pinfunction "58_58") (pintype "bidirectional"))
      (node (ref "Q101") (pin "3") (pinfunction "3_3") (pintype "passive"))
    )
    (net (code "30") (name "GND") (class "Default")
      (node (ref "C101") (pin "2") (pinfunction "2_2") (pintype "passive"))
      (node (ref "C102") (pin "2") (pinfunction "2_2") (pintype "passive"))
      (node (ref "C103") (pin "2") (pinfunction "2_2") (pintype "passive"))
      (node (ref "C104") (pin "-") (pinfunction "-_-") (pintype "passive"))
      (node (ref "C107") (pin "2") (pinfunction "2_2") (pintype "passive"))
      (node (ref "C110") (pin "2") (pinfunction "2_2") (pintype "passive"))
      (node (ref "C111") (pin "2") (pinfunction "2_2") (pintype "passive"))
      (node (ref "C112") (pin "2") (pinfunction "2_2") (pintype "passive"))
      (node (ref "C113") (pin "2") (pinfunction "2_2") (pintype "passive"))
      (node (ref "C121") (pin "2") (pinfunction "2_2") (pintype "passive"))
      (node (ref "C122") (pin "1") (pinfunction "1_1") (pintype "passive"))
      (node (ref "C123") (pin "1") (pinfunction "1_1") (pintype "passive"))
      (node (ref "C14") (pin "2") (pinfunction "2_2") (pintype "passive"))
      (node (ref "C15") (pin "2") (pinfunction "2_2") (pintype "passive"))
      (node (ref "C16") (pin "2") (pinfunction "2_2") (pintype "passive"))
      (node (ref "C17") (pin "2") (pinfunction "2_2") (pintype "passive"))
      (node (ref "C18") (pin "1") (pinfunction "1_1") (pintype "passive"))
      (node (ref "C19") (pin "1") (pinfunction "1_1") (pintype "passive"))
      (node (ref "C20") (pin "2") (pinfunction "2_2") (pintype "passive"))
      (node (ref "C21") (pin "2") (pinfunction "2_2") (pintype "passive"))
      (node (ref "C23") (pin "2") (pinfunction "2_2") (pintype "passive"))
      (node (ref "C24") (pin "2") (pinfunction "2_2") (pintype "passive"))
      (node (ref "C25") (pin "1") (pinfunction "1_1") (pintype "passive"))
      (node (ref "C26") (pin "1") (pinfunction "1_1") (pintype "passive"))
      (node (ref "C27") (pin "-") (pinfunction "-_-") (pintype "passive"))
      (node (ref "C28") (pin "1") (pinfunction "1_1") (pintype "passive"))
      (node (ref "C29") (pin "2") (pinfunction "2_2") (pintype "passive"))
      (node (ref "C30") (pin "-") (pinfunction "-_-") (pintype "passive"))
      (node (ref "C31") (pin "1") (pinfunction "1_1") (pintype "passive"))
      (node (ref "C401") (pin "1") (pinfunction "1_1") (pintype "passive"))
      (node (ref "C402") (pin "2") (pinfunction "2_2") (pintype "passive"))
      (node (ref "C403") (pin "-") (pinfunction "-_-") (pintype "passive"))
      (node (ref "C404") (pin "1") (pinfunction "1_1") (pintype "passive"))
      (node (ref "C405") (pin "2") (pinfunction "2_2") (pintype "passive"))
      (node (ref "C406") (pin "2") (pinfunction "2_2") (pintype "passive"))
      (node (ref "C407") (pin "2") (pinfunction "2_2") (pintype "passive"))
      (node (ref "C408") (pin "2") (pinfunction "2_2") (pintype "passive"))
      (node (ref "C409") (pin "2") (pinfunction "2_2") (pintype "passive"))
      (node (ref "C410") (pin "2") (pinfunction "2_2") (pintype "passive"))
      (node (ref "C411") (pin "2") (pinfunction "2_2") (pintype "passive"))
      (node (ref "C412") (pin "2") (pinfunction "2_2") (pintype "passive"))
      (node (ref "IC401") (pin "27") (pinfunction "TSTPLL/48MCLK_27") (pintype "bidirectional"))
      (node (ref "IC401") (pin "28") (pinfunction "GND_28") (pintype "power_in"))
      (node (ref "IC401") (pin "31") (pinfunction "TSTMODE_31") (pintype "input"))
      (node (ref "IC401") (pin "7") (pinfunction "GND_7") (pintype "power_in"))
      (node (ref "J1") (pin "4") (pinfunction "4_4") (pintype "passive"))
      (node (ref "J10") (pin "1") (pinfunction "1_1") (pintype "passive"))
      (node (ref "J10") (pin "2") (pinfunction "2_2") (pintype "passive"))
      (node (ref "J3") (pin "1") (pinfunction "1_1") (pintype "passive"))
      (node (ref "J3") (pin "2") (pinfunction "2_2") (pintype "passive"))
      (node (ref "J401") (pin "GND") (pinfunction "GND_GND") (pintype "input"))
      (node (ref "J5") (pin "2") (pinfunction "2_2") (pintype "passive"))
      (node (ref "JP3") (pin "1") (pinfunction "1_1") (pintype "passive"))
      (node (ref "JP3") (pin "2") (pinfunction "2_2") (pintype "passive"))
      (node (ref "LED1") (pin "C") (pinfunction "C_C") (pintype "passive"))
      (node (ref "LED101") (pin "C") (pinfunction "C_C") (pintype "passive"))
      (node (ref "LED102") (pin "C") (pinfunction "C_C") (pintype "passive"))
      (node (ref "LED2") (pin "C") (pinfunction "C_C") (pintype "passive"))
      (node (ref "MSP101") (pin "14") (pinfunction "14_14") (pintype "power_in"))
      (node (ref "MSP101") (pin "16") (pinfunction "16_16") (pintype "power_in"))
      (node (ref "MSP101") (pin "39") (pinfunction "39_39") (pintype "power_in"))
      (node (ref "MSP101") (pin "49") (pinfunction "49_49") (pintype "power_in"))
      (node (ref "MSP101") (pin "56") (pinfunction "56_56") (pintype "power_in"))
      (node (ref "MSP101") (pin "TP") (pinfunction "TP_TP") (pintype "power_in"))
      (node (ref "Q101") (pin "2") (pinfunction "2_2") (pintype "passive"))
      (node (ref "Q2") (pin "P3") (pinfunction "GND_P3") (pintype "power_in"))
      (node (ref "Q4") (pin "2") (pinfunction "2_2") (pintype "passive"))
      (node (ref "Q401") (pin "2") (pinfunction "2_2") (pintype "passive"))
      (node (ref "R106") (pin "1") (pinfunction "1_1") (pintype "passive"))
      (node (ref "R122") (pin "2") (pinfunction "2_2") (pintype "passive"))
      (node (ref "R125") (pin "2") (pinfunction "2_2") (pintype "passive"))
      (node (ref "R16") (pin "1") (pinfunction "1_1") (pintype "passive"))
      (node (ref "R401") (pin "2") (pinfunction "2_2") (pintype "passive"))
      (node (ref "R408") (pin "1") (pinfunction "1_1") (pintype "passive"))
      (node (ref "R409") (pin "1") (pinfunction "1_1") (pintype "passive"))
      (node (ref "R412") (pin "1") (pinfunction "1_1") (pintype "passive"))
      (node (ref "R413") (pin "1") (pinfunction "1_1") (pintype "passive"))
      (node (ref "R414") (pin "2") (pinfunction "2_2") (pintype "passive"))
      (node (ref "R415") (pin "2") (pinfunction "2_2") (pintype "passive"))
      (node (ref "R418") (pin "2") (pinfunction "2_2") (pintype "passive"))
      (node (ref "R419") (pin "2") (pinfunction "2_2") (pintype "passive"))
      (node (ref "S1") (pin "2") (pinfunction "S_2") (pintype "passive"))
      (node (ref "S2") (pin "2") (pinfunction "S_2") (pintype "passive"))
      (node (ref "S3") (pin "1") (pinfunction "P_1") (pintype "passive"))
      (node (ref "TP104") (pin "1") (pinfunction "1_1") (pintype "passive"))
      (node (ref "U402") (pin "1") (pinfunction "MODE_1") (pintype "input"))
      (node (ref "U402") (pin "4") (pinfunction "GND_4") (pintype "power_in"))
      (node (ref "U404") (pin "4") (pinfunction "GND_4") (pintype "power_in"))
      (node (ref "U6") (pin "14") (pinfunction "14_14") (pintype "power_in"))
      (node (ref "U6") (pin "19") (pinfunction "19_19") (pintype "power_in"))
      (node (ref "U6") (pin "49") (pinfunction "49_49") (pintype "power_in"))
      (node (ref "U6") (pin "61") (pinfunction "61_61") (pintype "power_in"))
      (node (ref "U6") (pin "68") (pinfunction "68_68") (pintype "power_in"))
    )
    (net (code "31") (name "HUB_DM1") (class "Default")
      (node (ref "R31") (pin "1") (pinfunction "1_1") (pintype "passive"))
      (node (ref "R416") (pin "2") (pinfunction "2_2") (pintype "passive"))
      (node (ref "R419") (pin "1") (pinfunction "1_1") (pintype "passive"))
    )
    (net (code "32") (name "HUB_DM2") (class "Default")
      (node (ref "R103") (pin "1") (pinfunction "1_1") (pintype "passive"))
      (node (ref "R410") (pin "2") (pinfunction "2_2") (pintype "passive"))
      (node (ref "R415") (pin "1") (pinfunction "1_1") (pintype "passive"))
    )
    (net (code "33") (name "HUB_DP1") (class "Default")
      (node (ref "R32") (pin "1") (pinfunction "1_1") (pintype "passive"))
      (node (ref "R417") (pin "2") (pinfunction "2_2") (pintype "passive"))
      (node (ref "R418") (pin "1") (pinfunction "1_1") (pintype "passive"))
    )
    (net (code "34") (name "HUB_DP2") (class "Default")
      (node (ref "R104") (pin "1") (pinfunction "1_1") (pintype "passive"))
      (node (ref "R411") (pin "2") (pinfunction "2_2") (pintype "passive"))
      (node (ref "R414") (pin "1") (pinfunction "1_1") (pintype "passive"))
    )
    (net (code "35") (name "Net-(C15-Pad1)") (class "Default")
      (node (ref "C15") (pin "1") (pinfunction "1_1") (pintype "passive"))
      (node (ref "U6") (pin "67") (pinfunction "67_67") (pintype "power_in"))
    )
    (net (code "36") (name "Net-(C16-Pad1)") (class "Default")
      (node (ref "C16") (pin "1") (pinfunction "1_1") (pintype "passive"))
      (node (ref "U6") (pin "66") (pinfunction "66_66") (pintype "power_in"))
    )
    (net (code "37") (name "Net-(C18-Pad2)") (class "Default")
      (node (ref "C18") (pin "2") (pinfunction "2_2") (pintype "passive"))
      (node (ref "U6") (pin "20") (pinfunction "20_20") (pintype "power_in"))
    )
    (net (code "38") (name "Net-(C29-Pad1)") (class "Default")
      (node (ref "C29") (pin "1") (pinfunction "1_1") (pintype "passive"))
      (node (ref "R28") (pin "1") (pinfunction "1_1") (pintype "passive"))
      (node (ref "U6") (pin "11") (pinfunction "11_11") (pintype "power_in"))
    )
    (net (code "39") (name "Net-(C101-Pad1)") (class "Default")
      (node (ref "C101") (pin "1") (pinfunction "1_1") (pintype "passive"))
      (node (ref "MSP101") (pin "17") (pinfunction "17_17") (pintype "power_in"))
    )
    (net (code "40") (name "Net-(IC401-DM0)") (class "Default")
      (node (ref "C406") (pin "1") (pinfunction "1_1") (pintype "passive"))
      (node (ref "IC401") (pin "2") (pinfunction "DM0_2") (pintype "bidirectional"))
      (node (ref "R406") (pin "1") (pinfunction "1_1") (pintype "passive"))
    )
    (net (code "41") (name "Net-(IC401-DM1)") (class "Default")
      (node (ref "C412") (pin "1") (pinfunction "1_1") (pintype "passive"))
      (node (ref "IC401") (pin "11") (pinfunction "DM1_11") (pintype "bidirectional"))
      (node (ref "R416") (pin "1") (pinfunction "1_1") (pintype "passive"))
    )
    (net (code "42") (name "Net-(IC401-DM2)") (class "Default")
      (node (ref "C410") (pin "1") (pinfunction "1_1") (pintype "passive"))
      (node (ref "IC401") (pin "15") (pinfunction "DM2_15") (pintype "bidirectional"))
      (node (ref "R410") (pin "1") (pinfunction "1_1") (pintype "passive"))
    )
    (net (code "43") (name "Net-(IC401-DM3)") (class "Default")
      (node (ref "IC401") (pin "19") (pinfunction "DM3_19") (pintype "bidirectional"))
      (node (ref "R413") (pin "2") (pinfunction "2_2") (pintype "passive"))
    )
    (net (code "44") (name "Net-(IC401-DM4)") (class "Default")
      (node (ref "IC401") (pin "23") (pinfunction "DM4_23") (pintype "bidirectional"))
      (node (ref "R409") (pin "2") (pinfunction "2_2") (pintype "passive"))
    )
    (net (code "45") (name "Net-(IC401-DP0)") (class "Default")
      (node (ref "C405") (pin "1") (pinfunction "1_1") (pintype "passive"))
      (node (ref "IC401") (pin "1") (pinfunction "DP0_1") (pintype "bidirectional"))
      (node (ref "R403") (pin "2") (pinfunction "2_2") (pintype "passive"))
      (node (ref "R405") (pin "1") (pinfunction "1_1") (pintype "passive"))
    )
    (net (code "46") (name "Net-(IC401-DP1)") (class "Default")
      (node (ref "C411") (pin "1") (pinfunction "1_1") (pintype "passive"))
      (node (ref "IC401") (pin "12") (pinfunction "DP1_12") (pintype "bidirectional"))
      (node (ref "R417") (pin "1") (pinfunction "1_1") (pintype "passive"))
    )
    (net (code "47") (name "Net-(IC401-DP2)") (class "Default")
      (node (ref "C409") (pin "1") (pinfunction "1_1") (pintype "passive"))
      (node (ref "IC401") (pin "16") (pinfunction "DP2_16") (pintype "bidirectional"))
      (node (ref "R411") (pin "1") (pinfunction "1_1") (pintype "passive"))
    )
    (net (code "48") (name "Net-(IC401-DP3)") (class "Default")
      (node (ref "IC401") (pin "20") (pinfunction "DP3_20") (pintype "bidirectional"))
      (node (ref "R412") (pin "2") (pinfunction "2_2") (pintype "passive"))
    )
    (net (code "49") (name "Net-(IC401-DP4)") (class "Default")
      (node (ref "IC401") (pin "24") (pinfunction "DP4_24") (pintype "bidirectional"))
      (node (ref "R408") (pin "2") (pinfunction "2_2") (pintype "passive"))
    )
    (net (code "50") (name "Net-(IC401-XTAL1)") (class "Default")
      (node (ref "IC401") (pin "30") (pinfunction "XTAL1_30") (pintype "input"))
      (node (ref "Q401") (pin "1") (pinfunction "1_1") (pintype "passive"))
    )
    (net (code "51") (name "Net-(IC401-XTAL2)") (class "Default")
      (node (ref "IC401") (pin "29") (pinfunction "XTAL2_29") (pintype "output"))
      (node (ref "R407") (pin "2") (pinfunction "2_2") (pintype "passive"))
    )
    (net (code "52") (name "Net-(IC401-~{RESET})") (class "Default")
      (node (ref "C408") (pin "1") (pinfunction "1_1") (pintype "passive"))
      (node (ref "IC401") (pin "4") (pinfunction "~{RESET}_4") (pintype "input"))
      (node (ref "R404") (pin "2") (pinfunction "2_2") (pintype "passive"))
    )
    (net (code "53") (name "Net-(J401-PadSHIELD1)") (class "Default")
      (node (ref "J401") (pin "SHIELD1") (pinfunction "SHIELD1_SHIELD1") (pintype "bidirectional"))
      (node (ref "R401") (pin "1") (pinfunction "1_1") (pintype "passive"))
    )
    (net (code "54") (name "Net-(JP8-Pad2)") (class "Default")
      (node (ref "JP8") (pin "2") (pinfunction "2_2") (pintype "passive"))
      (node (ref "R29") (pin "1") (pinfunction "1_1") (pintype "passive"))
    )
    (net (code "55") (name "Net-(L401-1)") (class "Default")
      (node (ref "L401") (pin "P$1") (pinfunction "1_P$1") (pintype "passive"))
      (node (ref "U402") (pin "2") (pinfunction "SW_2") (pintype "output"))
    )
    (net (code "56") (name "Net-(LED1-PadA)") (class "Default")
      (node (ref "LED1") (pin "A") (pinfunction "A_A") (pintype "passive"))
      (node (ref "R29") (pin "2") (pinfunction "2_2") (pintype "passive"))
    )
    (net (code "57") (name "Net-(LED2-PadA)") (class "Default")
      (node (ref "LED2") (pin "A") (pinfunction "A_A") (pintype "passive"))
      (node (ref "R30") (pin "2") (pinfunction "2_2") (pintype "passive"))
    )
    (net (code "58") (name "Net-(LED101-PadA)") (class "Default")
      (node (ref "LED101") (pin "A") (pinfunction "A_A") (pintype "passive"))
      (node (ref "R101") (pin "1") (pinfunction "1_1") (pintype "passive"))
    )
    (net (code "59") (name "Net-(LED102-PadA)") (class "Default")
      (node (ref "LED102") (pin "A") (pinfunction "A_A") (pintype "passive"))
      (node (ref "R102") (pin "1") (pinfunction "1_1") (pintype "passive"))
    )
    (net (code "60") (name "Net-(Q2-1)") (class "Default")
      (node (ref "C25") (pin "2") (pinfunction "2_2") (pintype "passive"))
      (node (ref "Q2") (pin "P1") (pinfunction "1_P1") (pintype "bidirectional"))
      (node (ref "U6") (pin "13") (pinfunction "13_13") (pintype "bidirectional"))
    )
    (net (code "61") (name "Net-(Q2-2)") (class "Default")
      (node (ref "C26") (pin "2") (pinfunction "2_2") (pintype "passive"))
      (node (ref "Q2") (pin "P2") (pinfunction "2_P2") (pintype "bidirectional"))
      (node (ref "U6") (pin "12") (pinfunction "12_12") (pintype "bidirectional"))
    )
    (net (code "62") (name "Net-(Q4-Pad1)") (class "Default")
      (node (ref "Q4") (pin "1") (pinfunction "1_1") (pintype "passive"))
      (node (ref "U6") (pin "70") (pinfunction "70_70") (pintype "bidirectional"))
    )
    (net (code "63") (name "Net-(Q4-Pad3)") (class "Default")
      (node (ref "Q4") (pin "3") (pinfunction "3_3") (pintype "passive"))
      (node (ref "U6") (pin "69") (pinfunction "69_69") (pintype "bidirectional"))
    )
    (net (code "64") (name "Net-(Q401-Pad3)") (class "Default")
      (node (ref "Q401") (pin "3") (pinfunction "3_3") (pintype "passive"))
      (node (ref "R407") (pin "1") (pinfunction "1_1") (pintype "passive"))
    )
    (net (code "65") (name "Net-(S5-S)") (class "Default")
      (node (ref "R14") (pin "1") (pinfunction "1_1") (pintype "passive"))
      (node (ref "S5") (pin "2") (pinfunction "S_2") (pintype "passive"))
    )
    (net (code "66") (name "Net-(U404-IO1)") (class "Default")
      (node (ref "J401") (pin "D-") (pinfunction "D-_D-") (pintype "input"))
      (node (ref "R406") (pin "2") (pinfunction "2_2") (pintype "passive"))
      (node (ref "U404") (pin "3") (pinfunction "IO1_3") (pintype "bidirectional"))
    )
    (net (code "67") (name "Net-(U404-IO2)") (class "Default")
      (node (ref "J401") (pin "D+") (pinfunction "D+_D+") (pintype "input"))
      (node (ref "R405") (pin "2") (pinfunction "2_2") (pintype "passive"))
      (node (ref "U404") (pin "5") (pinfunction "IO2_5") (pintype "bidirectional"))
    )
    (net (code "68") (name "P1.0") (class "Default")
      (node (ref "JP8") (pin "1") (pinfunction "1_1") (pintype "passive"))
      (node (ref "U6") (pin "21") (pinfunction "21_21") (pintype "bidirectional"))
    )
    (net (code "69") (name "P1.1") (class "Default")
      (node (ref "S2") (pin "1") (pinfunction "P_1") (pintype "passive"))
      (node (ref "U6") (pin "22") (pinfunction "22_22") (pintype "bidirectional"))
    )
    (net (code "70") (name "P1.2") (class "Default")
      (node (ref "J5") (pin "11") (pinfunction "11_11") (pintype "passive"))
      (node (ref "U6") (pin "23") (pinfunction "23_23") (pintype "bidirectional"))
    )
    (net (code "71") (name "P1.3") (class "Default")
      (node (ref "J5") (pin "9") (pinfunction "9_9") (pintype "passive"))
      (node (ref "U6") (pin "24") (pinfunction "24_24") (pintype "bidirectional"))
    )
    (net (code "72") (name "P1.4") (class "Default")
      (node (ref "J5") (pin "7") (pinfunction "7_7") (pintype "passive"))
      (node (ref "U6") (pin "25") (pinfunction "25_25") (pintype "bidirectional"))
    )
    (net (code "73") (name "P1.5") (class "Default")
      (node (ref "J5") (pin "5") (pinfunction "5_5") (pintype "passive"))
      (node (ref "U6") (pin "26") (pinfunction "26_26") (pintype "bidirectional"))
    )
    (net (code "74") (name "P1.6") (class "Default")
      (node (ref "J1") (pin "9") (pinfunction "9_9") (pintype "passive"))
      (node (ref "U6") (pin "27") (pinfunction "27_27") (pintype "bidirectional"))
    )
    (net (code "75") (name "P1.7") (class "Default")
      (node (ref "JP6.3") (pin "2") (pinfunction "2_2") (pintype "passive"))
      (node (ref "U6") (pin "28") (pinfunction "28_28") (pintype "bidirectional"))
    )
    (net (code "76") (name "P2.0") (class "Default")
      (node (ref "J5") (pin "4") (pinfunction "4_4") (pintype "passive"))
      (node (ref "U6") (pin "29") (pinfunction "29_29") (pintype "bidirectional"))
    )
    (net (code "77") (name "P2.1") (class "Default")
      (node (ref "S1") (pin "1") (pinfunction "P_1") (pintype "passive"))
      (node (ref "U6") (pin "30") (pinfunction "30_30") (pintype "bidirectional"))
    )
    (net (code "78") (name "P2.2") (class "Default")
      (node (ref "J5") (pin "6") (pinfunction "6_6") (pintype "passive"))
      (node (ref "U6") (pin "31") (pinfunction "31_31") (pintype "bidirectional"))
    )
    (net (code "79") (name "P2.3") (class "Default")
      (node (ref "J5") (pin "18") (pinfunction "18_18") (pintype "passive"))
      (node (ref "U6") (pin "32") (pinfunction "32_32") (pintype "bidirectional"))
    )
    (net (code "80") (name "P2.4") (class "Default")
      (node (ref "J5") (pin "3") (pinfunction "3_3") (pintype "passive"))
      (node (ref "U6") (pin "33") (pinfunction "33_33") (pintype "bidirectional"))
    )
    (net (code "81") (name "P2.5") (class "Default")
      (node (ref "J5") (pin "1") (pinfunction "1_1") (pintype "passive"))
      (node (ref "U6") (pin "34") (pinfunction "34_34") (pintype "bidirectional"))
    )
    (net (code "82") (name "P2.6") (class "Default")
      (node (ref "J5") (pin "16") (pinfunction "16_16") (pintype "passive"))
      (node (ref "U6") (pin "35") (pinfunction "35_35") (pintype "bidirectional"))
    )
    (net (code "83") (name "P2.7") (class "Default")
      (node (ref "J1") (pin "15") (pinfunction "15_15") (pintype "passive"))
      (node (ref "U6") (pin "36") (pinfunction "36_36") (pintype "bidirectional"))
    )
    (net (code "84") (name "P3.0") (class "Default")
      (node (ref "J5") (pin "12") (pinfunction "12_12") (pintype "passive"))
      (node (ref "U6") (pin "37") (pinfunction "37_37") (pintype "bidirectional"))
    )
    (net (code "85") (name "P3.1") (class "Default")
      (node (ref "J5") (pin "14") (pinfunction "14_14") (pintype "passive"))
      (node (ref "U6") (pin "38") (pinfunction "38_38") (pintype "bidirectional"))
    )
    (net (code "86") (name "P3.2") (class "Default")
      (node (ref "J1") (pin "13") (pinfunction "13_13") (pintype "passive"))
      (node (ref "U6") (pin "39") (pinfunction "39_39") (pintype "bidirectional"))
    )
    (net (code "87") (name "P3.3") (class "Default")
      (node (ref "J1") (pin "7") (pinfunction "7_7") (pintype "passive"))
      (node (ref "U6") (pin "40") (pinfunction "40_40") (pintype "bidirectional"))
    )
    (net (code "88") (name "P3.4") (class "Default")
      (node (ref "J1") (pin "5") (pinfunction "5_5") (pintype "passive"))
      (node (ref "U6") (pin "41") (pinfunction "41_41") (pintype "bidirectional"))
    )
    (net (code "89") (name "P3.5") (class "Default")
      (node (ref "J1") (pin "20") (pinfunction "20_20") (pintype "passive"))
      (node (ref "U6") (pin "42") (pinfunction "42_42") (pintype "bidirectional"))
    )
    (net (code "90") (name "P3.6") (class "Default")
      (node (ref "J1") (pin "18") (pinfunction "18_18") (pintype "passive"))
      (node (ref "U6") (pin "43") (pinfunction "43_43") (pintype "bidirectional"))
    )
    (net (code "91") (name "P3.7") (class "Default")
      (node (ref "J5") (pin "17") (pinfunction "17_17") (pintype "passive"))
      (node (ref "U6") (pin "44") (pinfunction "44_44") (pintype "bidirectional"))
    )
    (net (code "92") (name "P4.0") (class "Default")
      (node (ref "J5") (pin "15") (pinfunction "15_15") (pintype "passive"))
      (node (ref "U6") (pin "45") (pinfunction "45_45") (pintype "bidirectional"))
    )
    (net (code "93") (name "P4.1") (class "Default")
      (node (ref "J1") (pin "19") (pinfunction "19_19") (pintype "passive"))
      (node (ref "U6") (pin "46") (pinfunction "46_46") (pintype "bidirectional"))
    )
    (net (code "94") (name "P4.2") (class "Default")
      (node (ref "J1") (pin "17") (pinfunction "17_17") (pintype "passive"))
      (node (ref "U6") (pin "47") (pinfunction "47_47") (pintype "bidirectional"))
    )
    (net (code "95") (name "P4.3") (class "Default")
      (node (ref "J5") (pin "13") (pinfunction "13_13") (pintype "passive"))
      (node (ref "U6") (pin "48") (pinfunction "48_48") (pintype "bidirectional"))
    )
    (net (code "96") (name "P4.4{slash}UCA1TXD") (class "Default")
      (node (ref "JP6.1") (pin "2") (pinfunction "2_2") (pintype "passive"))
      (node (ref "U6") (pin "51") (pinfunction "51_51") (pintype "bidirectional"))
    )
    (net (code "97") (name "P4.5{slash}UCA1RXD") (class "Default")
      (node (ref "JP6.2") (pin "2") (pinfunction "2_2") (pintype "passive"))
      (node (ref "U6") (pin "52") (pinfunction "52_52") (pintype "bidirectional"))
    )
    (net (code "98") (name "P4.7") (class "Default")
      (node (ref "R30") (pin "1") (pinfunction "1_1") (pintype "passive"))
      (node (ref "U6") (pin "54") (pinfunction "54_54") (pintype "bidirectional"))
    )
    (net (code "99") (name "P6.0") (class "Default")
      (node (ref "J1") (pin "6") (pinfunction "6_6") (pintype "passive"))
      (node (ref "U6") (pin "77") (pinfunction "77_77") (pintype "bidirectional"))
    )
    (net (code "100") (name "P6.1") (class "Default")
      (node (ref "J1") (pin "8") (pinfunction "8_8") (pintype "passive"))
      (node (ref "U6") (pin "78") (pinfunction "78_78") (pintype "bidirectional"))
    )
    (net (code "101") (name "P6.2") (class "Default")
      (node (ref "J1") (pin "10") (pinfunction "10_10") (pintype "passive"))
      (node (ref "U6") (pin "79") (pinfunction "79_79") (pintype "bidirectional"))
    )
    (net (code "102") (name "P6.3") (class "Default")
      (node (ref "J1") (pin "12") (pinfunction "12_12") (pintype "passive"))
      (node (ref "U6") (pin "80") (pinfunction "80_80") (pintype "bidirectional"))
    )
    (net (code "103") (name "P6.4") (class "Default")
      (node (ref "J1") (pin "14") (pinfunction "14_14") (pintype "passive"))
      (node (ref "U6") (pin "1") (pinfunction "1_1") (pintype "bidirectional"))
    )
    (net (code "104") (name "P6.5") (class "Default")
      (node (ref "J1") (pin "3") (pinfunction "3_3") (pintype "passive"))
      (node (ref "U6") (pin "2") (pinfunction "2_2") (pintype "bidirectional"))
    )
    (net (code "105") (name "P6.6") (class "Default")
      (node (ref "J1") (pin "11") (pinfunction "11_11") (pintype "passive"))
      (node (ref "U6") (pin "3") (pinfunction "3_3") (pintype "bidirectional"))
    )
    (net (code "106") (name "P6.7") (class "Default")
      (node (ref "JP6.4") (pin "2") (pinfunction "2_2") (pintype "passive"))
      (node (ref "U6") (pin "4") (pinfunction "4_4") (pintype "bidirectional"))
    )
    (net (code "107") (name "P7.0") (class "Default")
      (node (ref "J1") (pin "16") (pinfunction "16_16") (pintype "passive"))
      (node (ref "U6") (pin "5") (pinfunction "5_5") (pintype "bidirectional"))
    )
    (net (code "108") (name "P7.4") (class "Default")
      (node (ref "J5") (pin "8") (pinfunction "8_8") (pintype "passive"))
      (node (ref "U6") (pin "57") (pinfunction "57_57") (pintype "bidirectional"))
    )
    (net (code "109") (name "P8.1") (class "Default")
      (node (ref "J5") (pin "20") (pinfunction "20_20") (pintype "passive"))
      (node (ref "U6") (pin "16") (pinfunction "16_16") (pintype "bidirectional"))
    )
    (net (code "110") (name "P8.2") (class "Default")
      (node (ref "J5") (pin "19") (pinfunction "19_19") (pintype "passive"))
      (node (ref "U6") (pin "17") (pinfunction "17_17") (pintype "bidirectional"))
    )
    (net (code "111") (name "RST{slash}SBWTDIO") (class "Default")
      (node (ref "C17") (pin "1") (pinfunction "1_1") (pintype "passive"))
      (node (ref "J5") (pin "10") (pinfunction "10_10") (pintype "passive"))
      (node (ref "JP4.2") (pin "2") (pinfunction "2_2") (pintype "passive"))
      (node (ref "R27") (pin "1") (pinfunction "1_1") (pintype "passive"))
      (node (ref "S3") (pin "2") (pinfunction "S_2") (pintype "passive"))
      (node (ref "U6") (pin "76") (pinfunction "76_76") (pintype "bidirectional"))
    )
    (net (code "112") (name "TARGET_DM") (class "Default")
      (node (ref "C24") (pin "1") (pinfunction "1_1") (pintype "passive"))
      (node (ref "R31") (pin "2") (pinfunction "2_2") (pintype "passive"))
      (node (ref "U6") (pin "64") (pinfunction "64_64") (pintype "bidirectional"))
    )
    (net (code "113") (name "TARGET_DP") (class "Default")
      (node (ref "C23") (pin "1") (pinfunction "1_1") (pintype "passive"))
      (node (ref "R15") (pin "2") (pinfunction "2_2") (pintype "passive"))
      (node (ref "R32") (pin "2") (pinfunction "2_2") (pintype "passive"))
      (node (ref "U6") (pin "62") (pinfunction "62_62") (pintype "bidirectional"))
    )
    (net (code "114") (name "TARGET_PUR") (class "Default")
      (node (ref "R14") (pin "2") (pinfunction "2_2") (pintype "passive"))
      (node (ref "R15") (pin "1") (pinfunction "1_1") (pintype "passive"))
      (node (ref "R16") (pin "2") (pinfunction "2_2") (pintype "passive"))
      (node (ref "U6") (pin "63") (pinfunction "63_63") (pintype "bidirectional"))
    )
    (net (code "115") (name "TEST{slash}SBWTCK") (class "Default")
      (node (ref "JP4.1") (pin "2") (pinfunction "2_2") (pintype "passive"))
      (node (ref "U6") (pin "71") (pinfunction "71_71") (pintype "input"))
    )
    (net (code "116") (name "unconnected-(IC401-EECLK-Pad5)") (class "Default")
      (node (ref "IC401") (pin "5") (pinfunction "EECLK_5") (pintype "output"))
    )
    (net (code "117") (name "unconnected-(IC401-SUSPND-Pad32)") (class "Default")
      (node (ref "IC401") (pin "32") (pinfunction "SUSPND_32") (pintype "output"))
    )
    (net (code "118") (name "unconnected-(J401-PadNC)") (class "Default")
      (node (ref "J401") (pin "NC") (pinfunction "NC_NC") (pintype "input"))
    )
    (net (code "119") (name "unconnected-(J401-PadSHIELD2)") (class "Default")
      (node (ref "J401") (pin "SHIELD2") (pinfunction "SHIELD2_SHIELD2") (pintype "bidirectional"))
    )
    (net (code "120") (name "unconnected-(J401-PadSHIELD3)") (class "Default")
      (node (ref "J401") (pin "SHIELD3") (pinfunction "SHIELD3_SHIELD3") (pintype "bidirectional"))
    )
    (net (code "121") (name "unconnected-(J401-PadSHIELD4)") (class "Default")
      (node (ref "J401") (pin "SHIELD4") (pinfunction "SHIELD4_SHIELD4") (pintype "bidirectional"))
    )
    (net (code "122") (name "unconnected-(J401-PadSHIELD5)") (class "Default")
      (node (ref "J401") (pin "SHIELD5") (pinfunction "SHIELD5_SHIELD5") (pintype "bidirectional"))
    )
    (net (code "123") (name "unconnected-(J401-PadSHIELD6)") (class "Default")
      (node (ref "J401") (pin "SHIELD6") (pinfunction "SHIELD6_SHIELD6") (pintype "bidirectional"))
    )
    (net (code "124") (name "unconnected-(JP4.3-Pad2)") (class "Default")
      (node (ref "JP4.3") (pin "2") (pinfunction "2_2") (pintype "passive"))
    )
    (net (code "125") (name "unconnected-(MSP101-Pad3)") (class "Default")
      (node (ref "MSP101") (pin "3") (pinfunction "3_3") (pintype "bidirectional"))
    )
    (net (code "126") (name "unconnected-(MSP101-Pad4)") (class "Default")
      (node (ref "MSP101") (pin "4") (pinfunction "4_4") (pintype "bidirectional"))
    )
    (net (code "127") (name "unconnected-(MSP101-Pad5)") (class "Default")
      (node (ref "MSP101") (pin "5") (pinfunction "5_5") (pintype "bidirectional"))
    )
    (net (code "128") (name "unconnected-(MSP101-Pad6)") (class "Default")
      (node (ref "MSP101") (pin "6") (pinfunction "6_6") (pintype "bidirectional"))
    )
    (net (code "129") (name "unconnected-(MSP101-Pad7)") (class "Default")
      (node (ref "MSP101") (pin "7") (pinfunction "7_7") (pintype "bidirectional"))
    )
    (net (code "130") (name "unconnected-(MSP101-Pad8)") (class "Default")
      (node (ref "MSP101") (pin "8") (pinfunction "8_8") (pintype "bidirectional"))
    )
    (net (code "131") (name "unconnected-(MSP101-Pad10)") (class "Default")
      (node (ref "MSP101") (pin "10") (pinfunction "10_10") (pintype "bidirectional"))
    )
    (net (code "132") (name "unconnected-(MSP101-Pad12)") (class "Default")
      (node (ref "MSP101") (pin "12") (pinfunction "12_12") (pintype "bidirectional"))
    )
    (net (code "133") (name "unconnected-(MSP101-Pad13)") (class "Default")
      (node (ref "MSP101") (pin "13") (pinfunction "13_13") (pintype "bidirectional"))
    )
    (net (code "134") (name "unconnected-(MSP101-Pad18)") (class "Default")
      (node (ref "MSP101") (pin "18") (pinfunction "18_18") (pintype "bidirectional"))
    )
    (net (code "135") (name "unconnected-(MSP101-Pad19)") (class "Default")
      (node (ref "MSP101") (pin "19") (pinfunction "19_19") (pintype "bidirectional"))
    )
    (net (code "136") (name "unconnected-(MSP101-Pad22)") (class "Default")
      (node (ref "MSP101") (pin "22") (pinfunction "22_22") (pintype "bidirectional"))
    )
    (net (code "137") (name "unconnected-(MSP101-Pad23)") (class "Default")
      (node (ref "MSP101") (pin "23") (pinfunction "23_23") (pintype "bidirectional"))
    )
    (net (code "138") (name "unconnected-(MSP101-Pad24)") (class "Default")
      (node (ref "MSP101") (pin "24") (pinfunction "24_24") (pintype "bidirectional"))
    )
    (net (code "139") (name "unconnected-(MSP101-Pad25)") (class "Default")
      (node (ref "MSP101") (pin "25") (pinfunction "25_25") (pintype "bidirectional"))
    )
    (net (code "140") (name "unconnected-(MSP101-Pad26)") (class "Default")
      (node (ref "MSP101") (pin "26") (pinfunction "26_26") (pintype "bidirectional"))
    )
    (net (code "141") (name "unconnected-(MSP101-Pad27)") (class "Default")
      (node (ref "MSP101") (pin "27") (pinfunction "27_27") (pintype "bidirectional"))
    )
    (net (code "142") (name "unconnected-(MSP101-Pad28)") (class "Default")
      (node (ref "MSP101") (pin "28") (pinfunction "28_28") (pintype "bidirectional"))
    )
    (net (code "143") (name "unconnected-(MSP101-Pad29)") (class "Default")
      (node (ref "MSP101") (pin "29") (pinfunction "29_29") (pintype "bidirectional"))
    )
    (net (code "144") (name "unconnected-(MSP101-Pad30)") (class "Default")
      (node (ref "MSP101") (pin "30") (pinfunction "30_30") (pintype "bidirectional"))
    )
    (net (code "145") (name "unconnected-(MSP101-Pad31)") (class "Default")
      (node (ref "MSP101") (pin "31") (pinfunction "31_31") (pintype "bidirectional"))
    )
    (net (code "146") (name "unconnected-(MSP101-Pad34)") (class "Default")
      (node (ref "MSP101") (pin "34") (pinfunction "34_34") (pintype "bidirectional"))
    )
    (net (code "147") (name "unconnected-(MSP101-Pad35)") (class "Default")
      (node (ref "MSP101") (pin "35") (pinfunction "35_35") (pintype "bidirectional"))
    )
    (net (code "148") (name "unconnected-(MSP101-Pad36)") (class "Default")
      (node (ref "MSP101") (pin "36") (pinfunction "36_36") (pintype "bidirectional"))
    )
    (net (code "149") (name "unconnected-(MSP101-Pad41)") (class "Default")
      (node (ref "MSP101") (pin "41") (pinfunction "41_41") (pintype "bidirectional"))
    )
    (net (code "150") (name "unconnected-(MSP101-Pad42)") (class "Default")
      (node (ref "MSP101") (pin "42") (pinfunction "42_42") (pintype "bidirectional"))
    )
    (net (code "151") (name "unconnected-(MSP101-Pad46)") (class "Default")
      (node (ref "MSP101") (pin "46") (pinfunction "46_46") (pintype "bidirectional"))
    )
    (net (code "152") (name "unconnected-(MSP101-Pad47)") (class "Default")
      (node (ref "MSP101") (pin "47") (pinfunction "47_47") (pintype "bidirectional"))
    )
    (net (code "153") (name "unconnected-(MSP101-Pad48)") (class "Default")
      (node (ref "MSP101") (pin "48") (pinfunction "48_48") (pintype "bidirectional"))
    )
    (net (code "154") (name "unconnected-(U6-Pad6)") (class "Default")
      (node (ref "U6") (pin "6") (pinfunction "6_6") (pintype "bidirectional"))
    )
    (net (code "155") (name "unconnected-(U6-Pad7)") (class "Default")
      (node (ref "U6") (pin "7") (pinfunction "7_7") (pintype "bidirectional"))
    )
    (net (code "156") (name "unconnected-(U6-Pad8)") (class "Default")
      (node (ref "U6") (pin "8") (pinfunction "8_8") (pintype "bidirectional"))
    )
    (net (code "157") (name "unconnected-(U6-Pad9)") (class "Default")
      (node (ref "U6") (pin "9") (pinfunction "9_9") (pintype "bidirectional"))
    )
    (net (code "158") (name "unconnected-(U6-Pad10)") (class "Default")
      (node (ref "U6") (pin "10") (pinfunction "10_10") (pintype "bidirectional"))
    )
    (net (code "159") (name "unconnected-(U6-Pad15)") (class "Default")
      (node (ref "U6") (pin "15") (pinfunction "15_15") (pintype "bidirectional"))
    )
    (net (code "160") (name "unconnected-(U6-Pad53)") (class "Default")
      (node (ref "U6") (pin "53") (pinfunction "53_53") (pintype "bidirectional"))
    )
    (net (code "161") (name "unconnected-(U6-Pad55)") (class "Default")
      (node (ref "U6") (pin "55") (pinfunction "55_55") (pintype "bidirectional"))
    )
    (net (code "162") (name "unconnected-(U6-Pad56)") (class "Default")
      (node (ref "U6") (pin "56") (pinfunction "56_56") (pintype "bidirectional"))
    )
    (net (code "163") (name "unconnected-(U6-Pad58)") (class "Default")
      (node (ref "U6") (pin "58") (pinfunction "58_58") (pintype "bidirectional"))
    )
    (net (code "164") (name "unconnected-(U6-Pad59)") (class "Default")
      (node (ref "U6") (pin "59") (pinfunction "59_59") (pintype "bidirectional"))
    )
    (net (code "165") (name "unconnected-(U6-Pad60)") (class "Default")
      (node (ref "U6") (pin "60") (pinfunction "60_60") (pintype "bidirectional"))
    )
    (net (code "166") (name "unconnected-(U6-Pad72)") (class "Default")
      (node (ref "U6") (pin "72") (pinfunction "72_72") (pintype "bidirectional"))
    )
    (net (code "167") (name "unconnected-(U6-Pad73)") (class "Default")
      (node (ref "U6") (pin "73") (pinfunction "73_73") (pintype "bidirectional"))
    )
    (net (code "168") (name "unconnected-(U6-Pad74)") (class "Default")
      (node (ref "U6") (pin "74") (pinfunction "74_74") (pintype "bidirectional"))
    )
    (net (code "169") (name "unconnected-(U6-Pad75)") (class "Default")
      (node (ref "U6") (pin "75") (pinfunction "75_75") (pintype "bidirectional"))
    )
    (net (code "170") (name "unconnected-(U404-NC-Pad2)") (class "Default")
      (node (ref "U404") (pin "2") (pinfunction "NC_2") (pintype "no_connect"))
    )
    (net (code "171") (name "~{OC}") (class "Default")
      (node (ref "IC401") (pin "10") (pinfunction "~{OVRCUR1}_10") (pintype "input"))
      (node (ref "IC401") (pin "14") (pinfunction "~{OVRCUR2}_14") (pintype "input"))
      (node (ref "IC401") (pin "18") (pinfunction "~{OVRCUR3}_18") (pintype "input"))
      (node (ref "IC401") (pin "22") (pinfunction "~{OVRCUR4}_22") (pintype "input"))
      (node (ref "R402") (pin "2") (pinfunction "2_2") (pintype "passive"))
    )
    (net (code "172") (name "~{PWRON}") (class "Default")
      (node (ref "IC401") (pin "13") (pinfunction "~{PWRON2}_13") (pintype "output"))
      (node (ref "IC401") (pin "17") (pinfunction "~{PWRON3}_17") (pintype "output"))
      (node (ref "IC401") (pin "21") (pinfunction "~{PWRON4}_21") (pintype "output"))
      (node (ref "IC401") (pin "9") (pinfunction "~{PWRON1}_9") (pintype "output"))
    )
  )
)
